# Goldfish_BigBoard_2-_revisions_after_pro.net
KiCad netlist of a schematic drawn in EAGLE
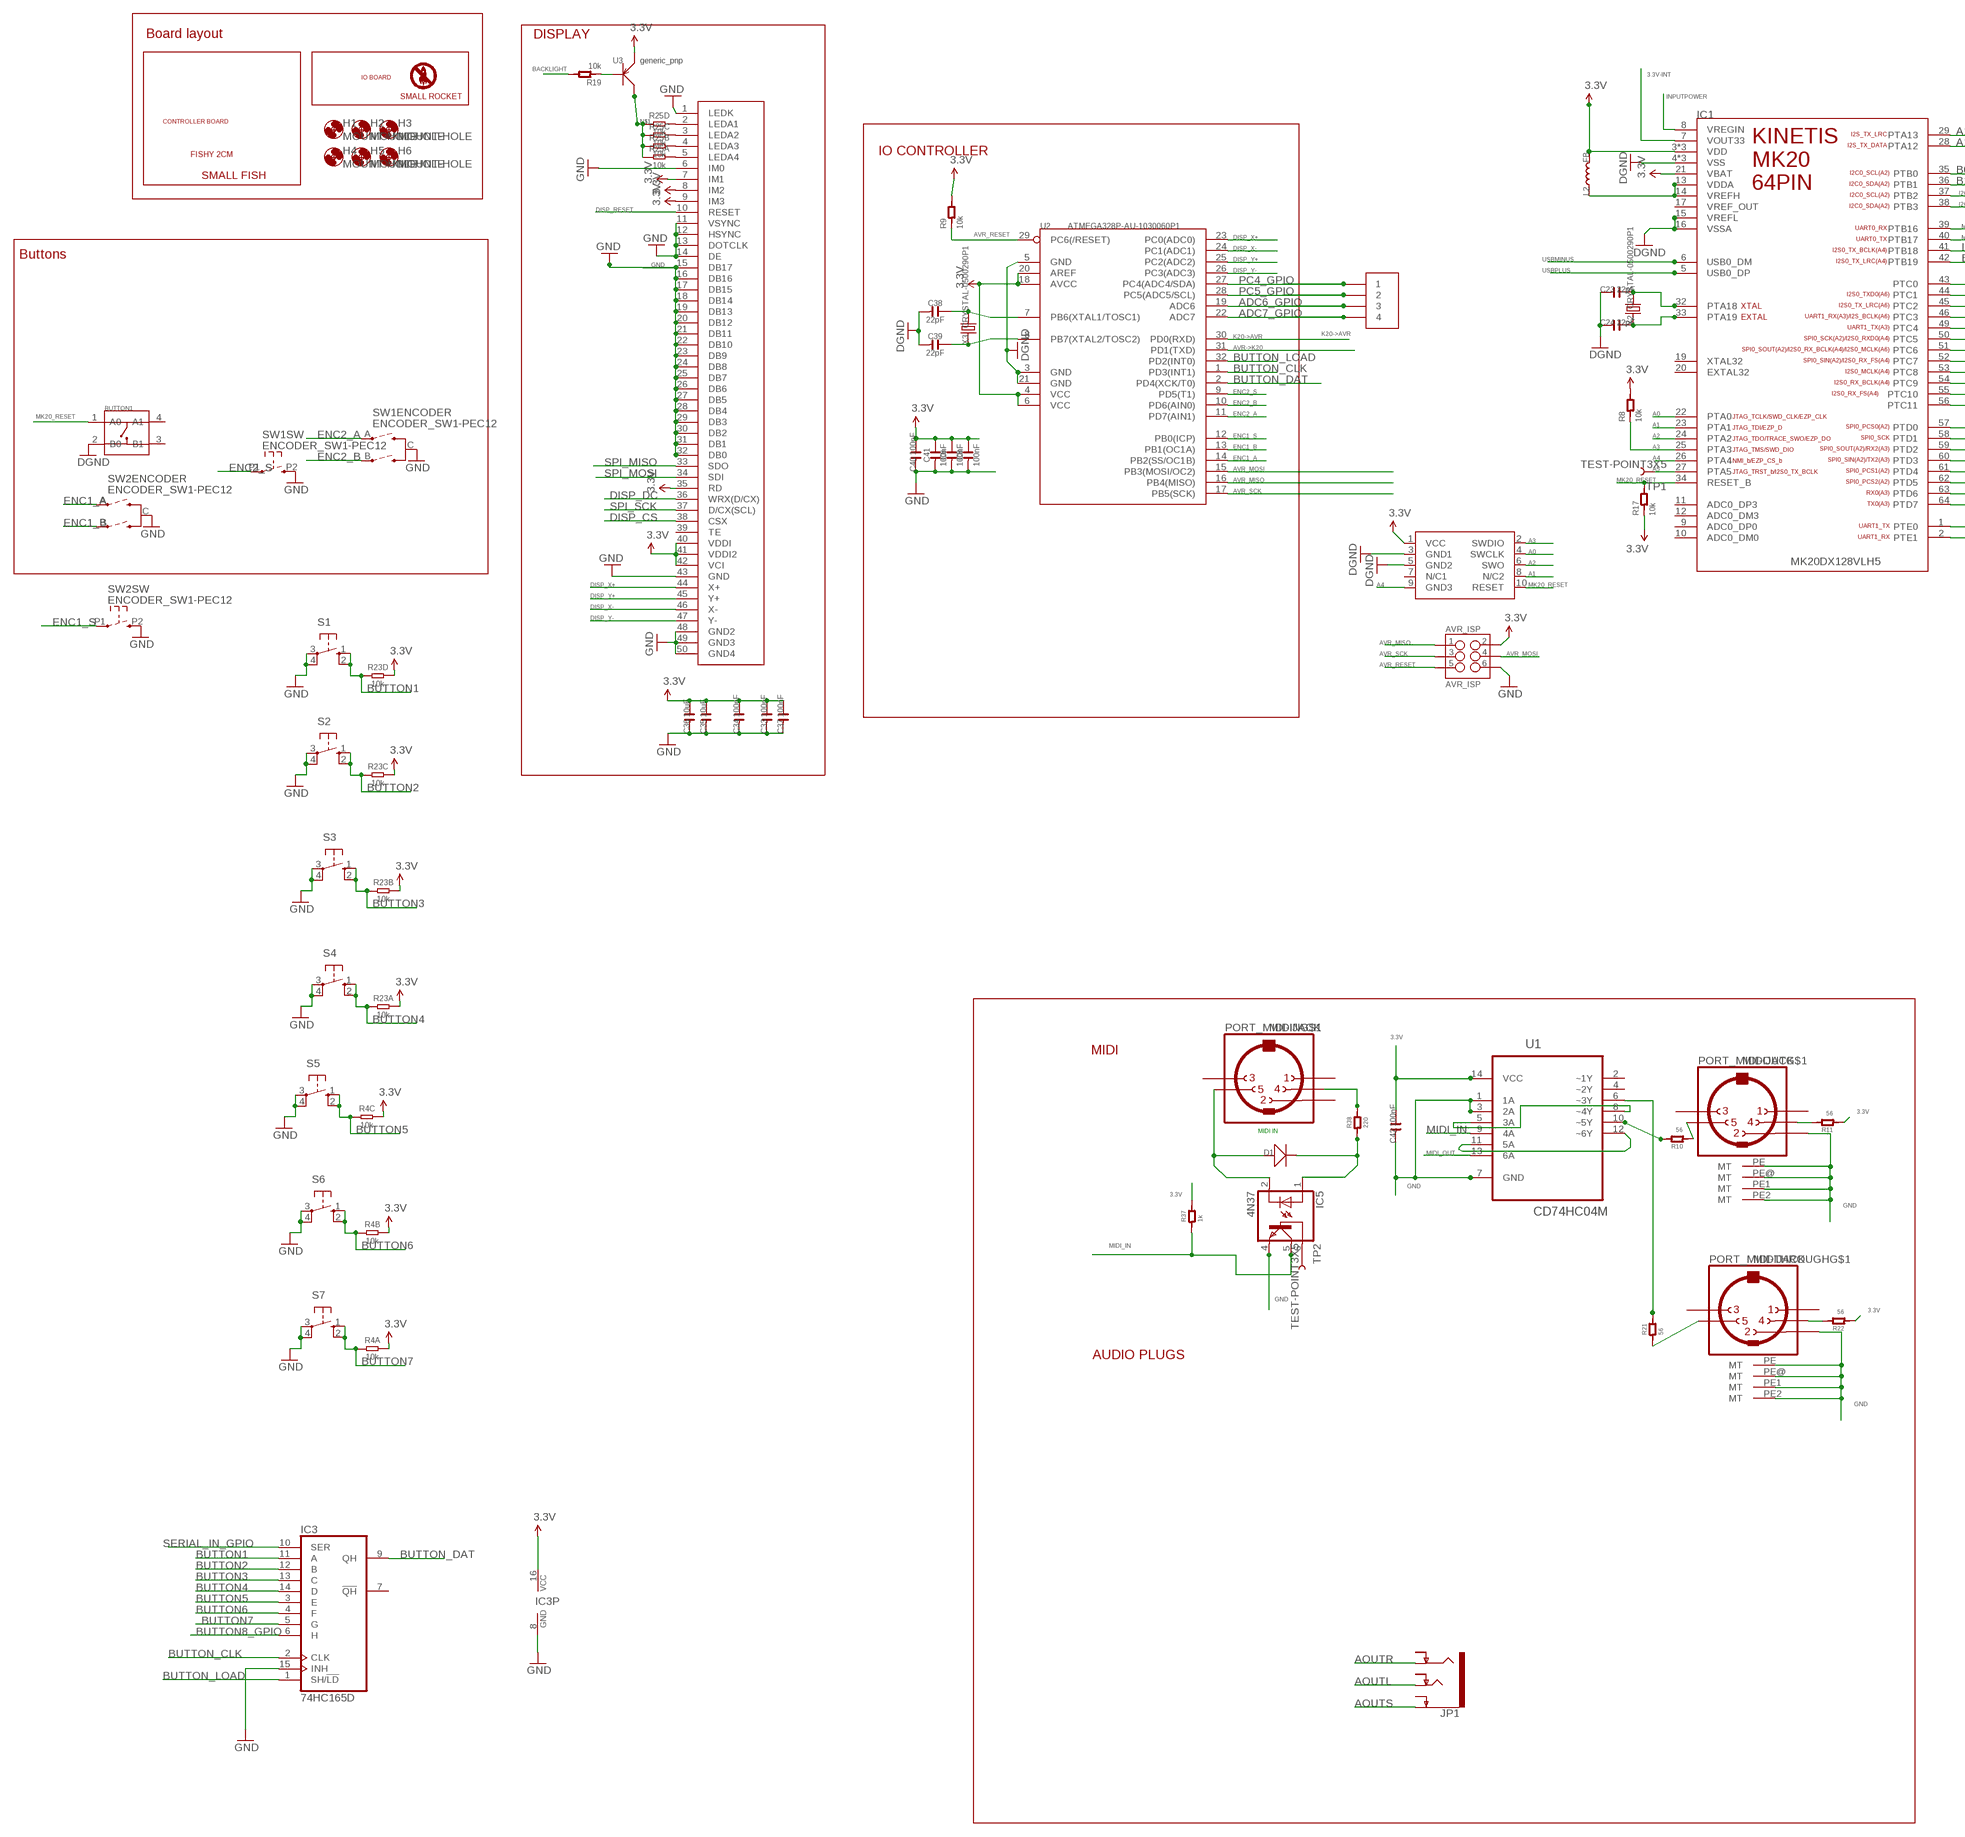
[diagram p0: schematic, sheet 1, part 1 of 3]
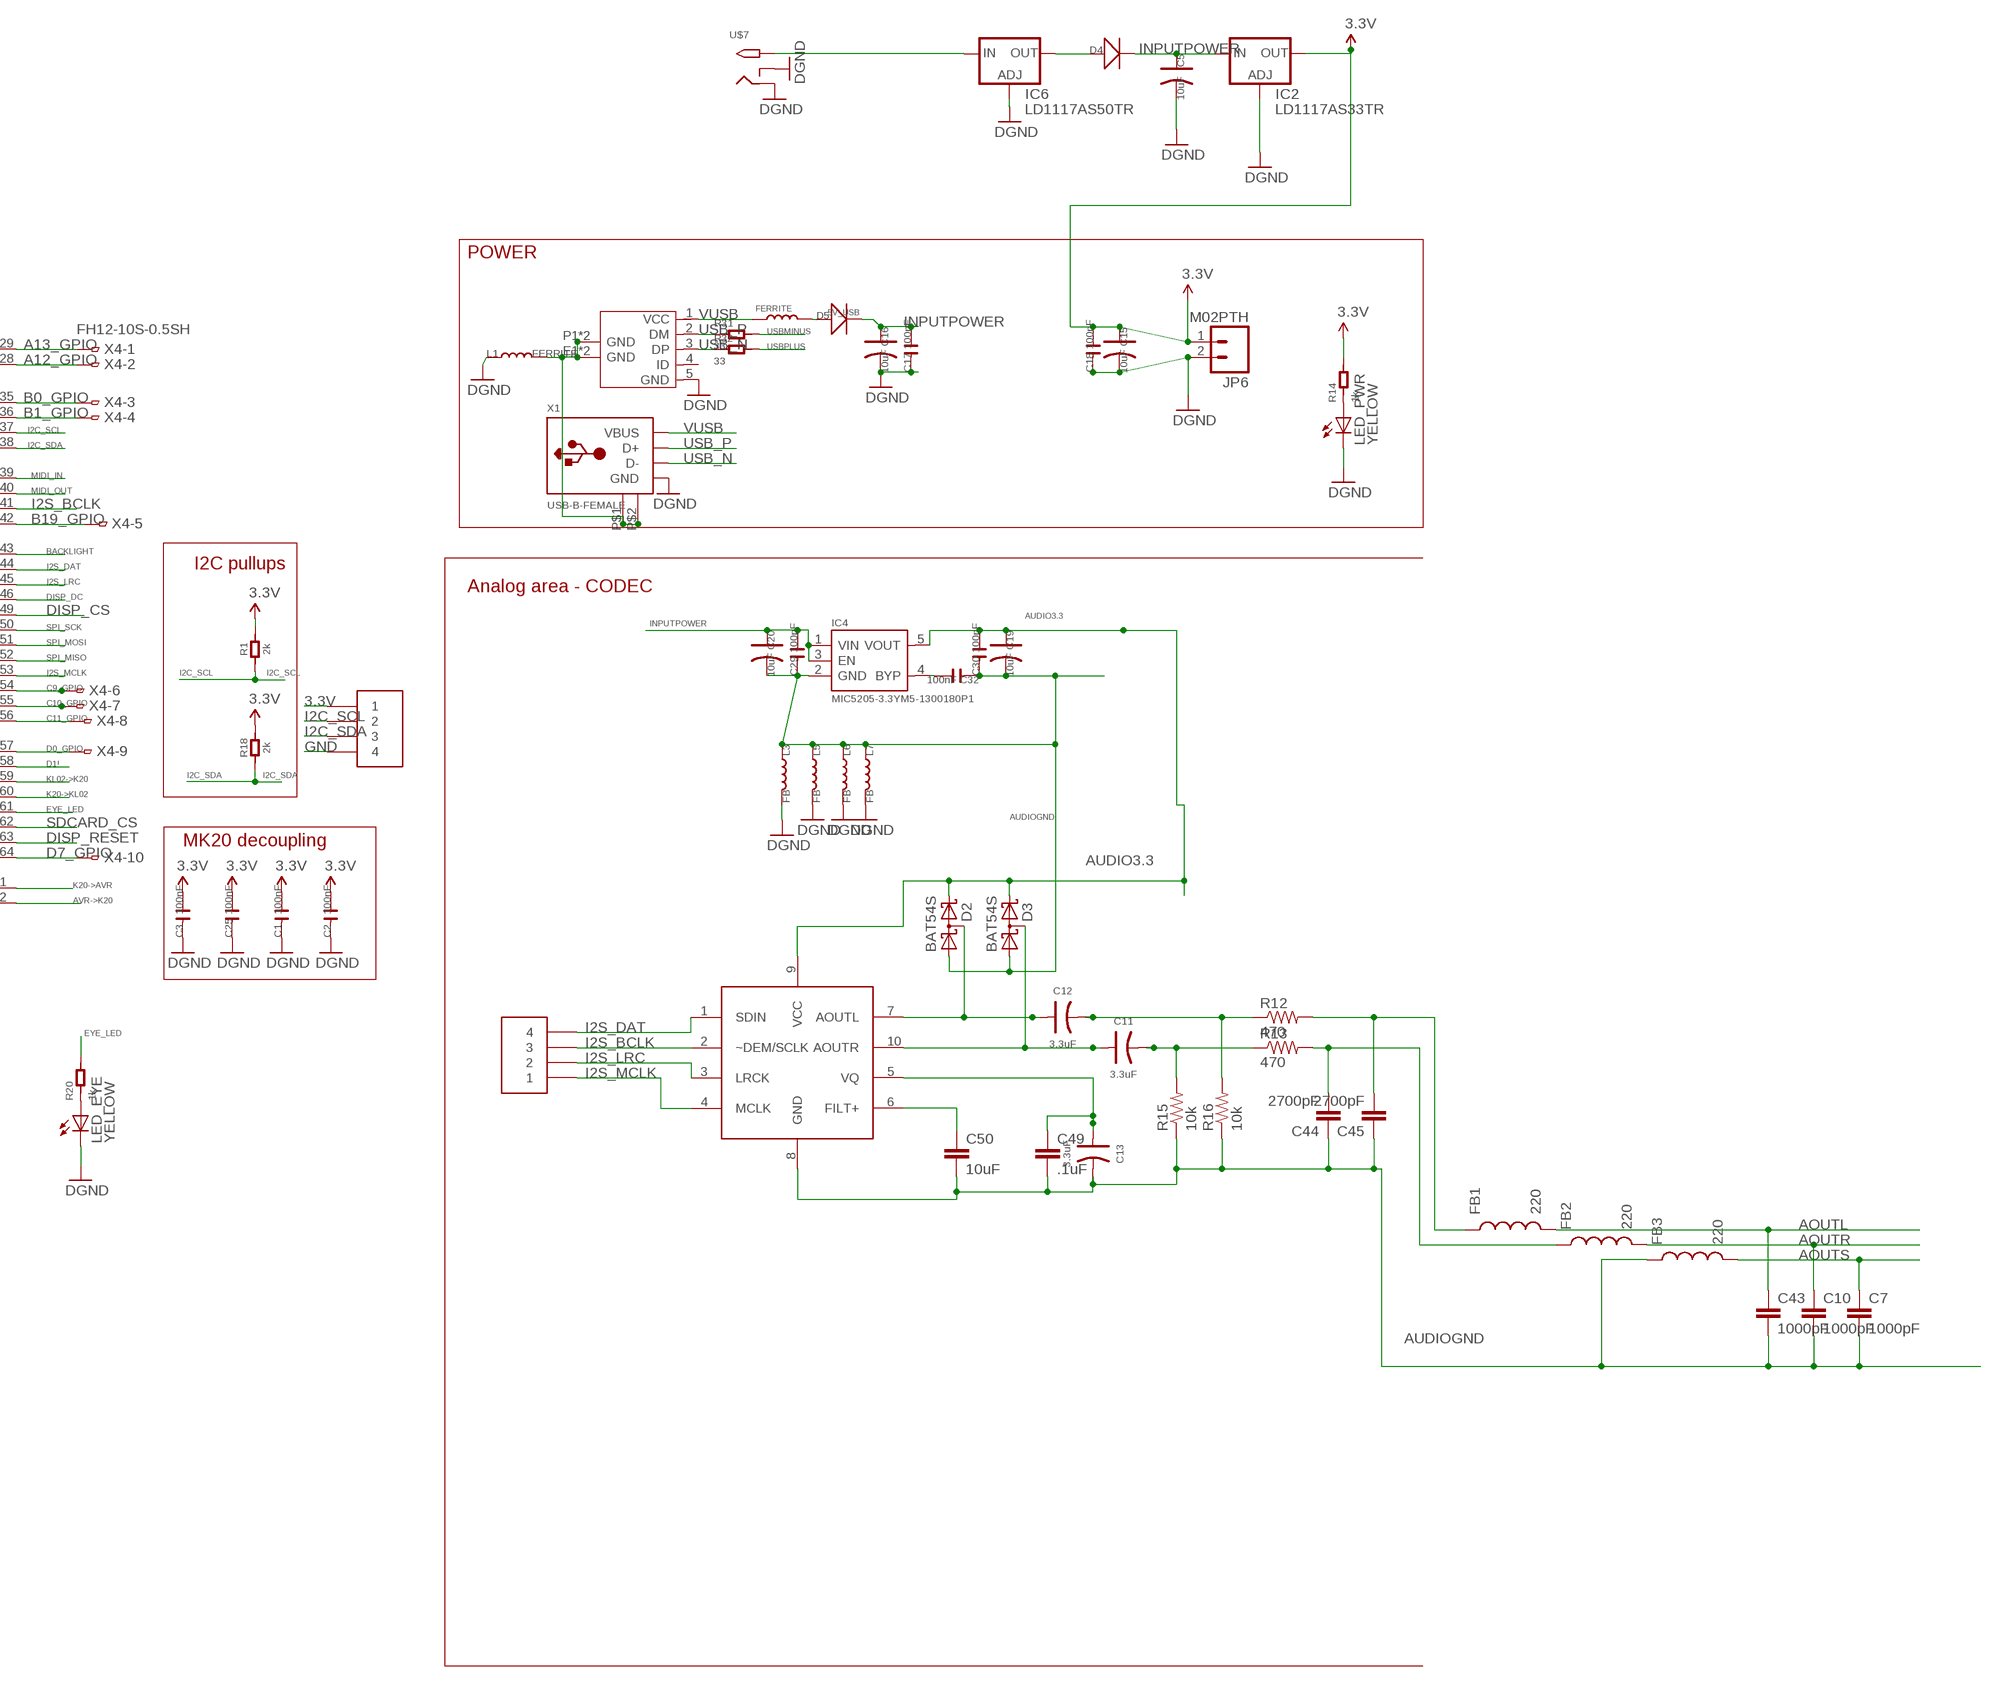
[diagram p1: schematic, sheet 1, part 2 of 3]
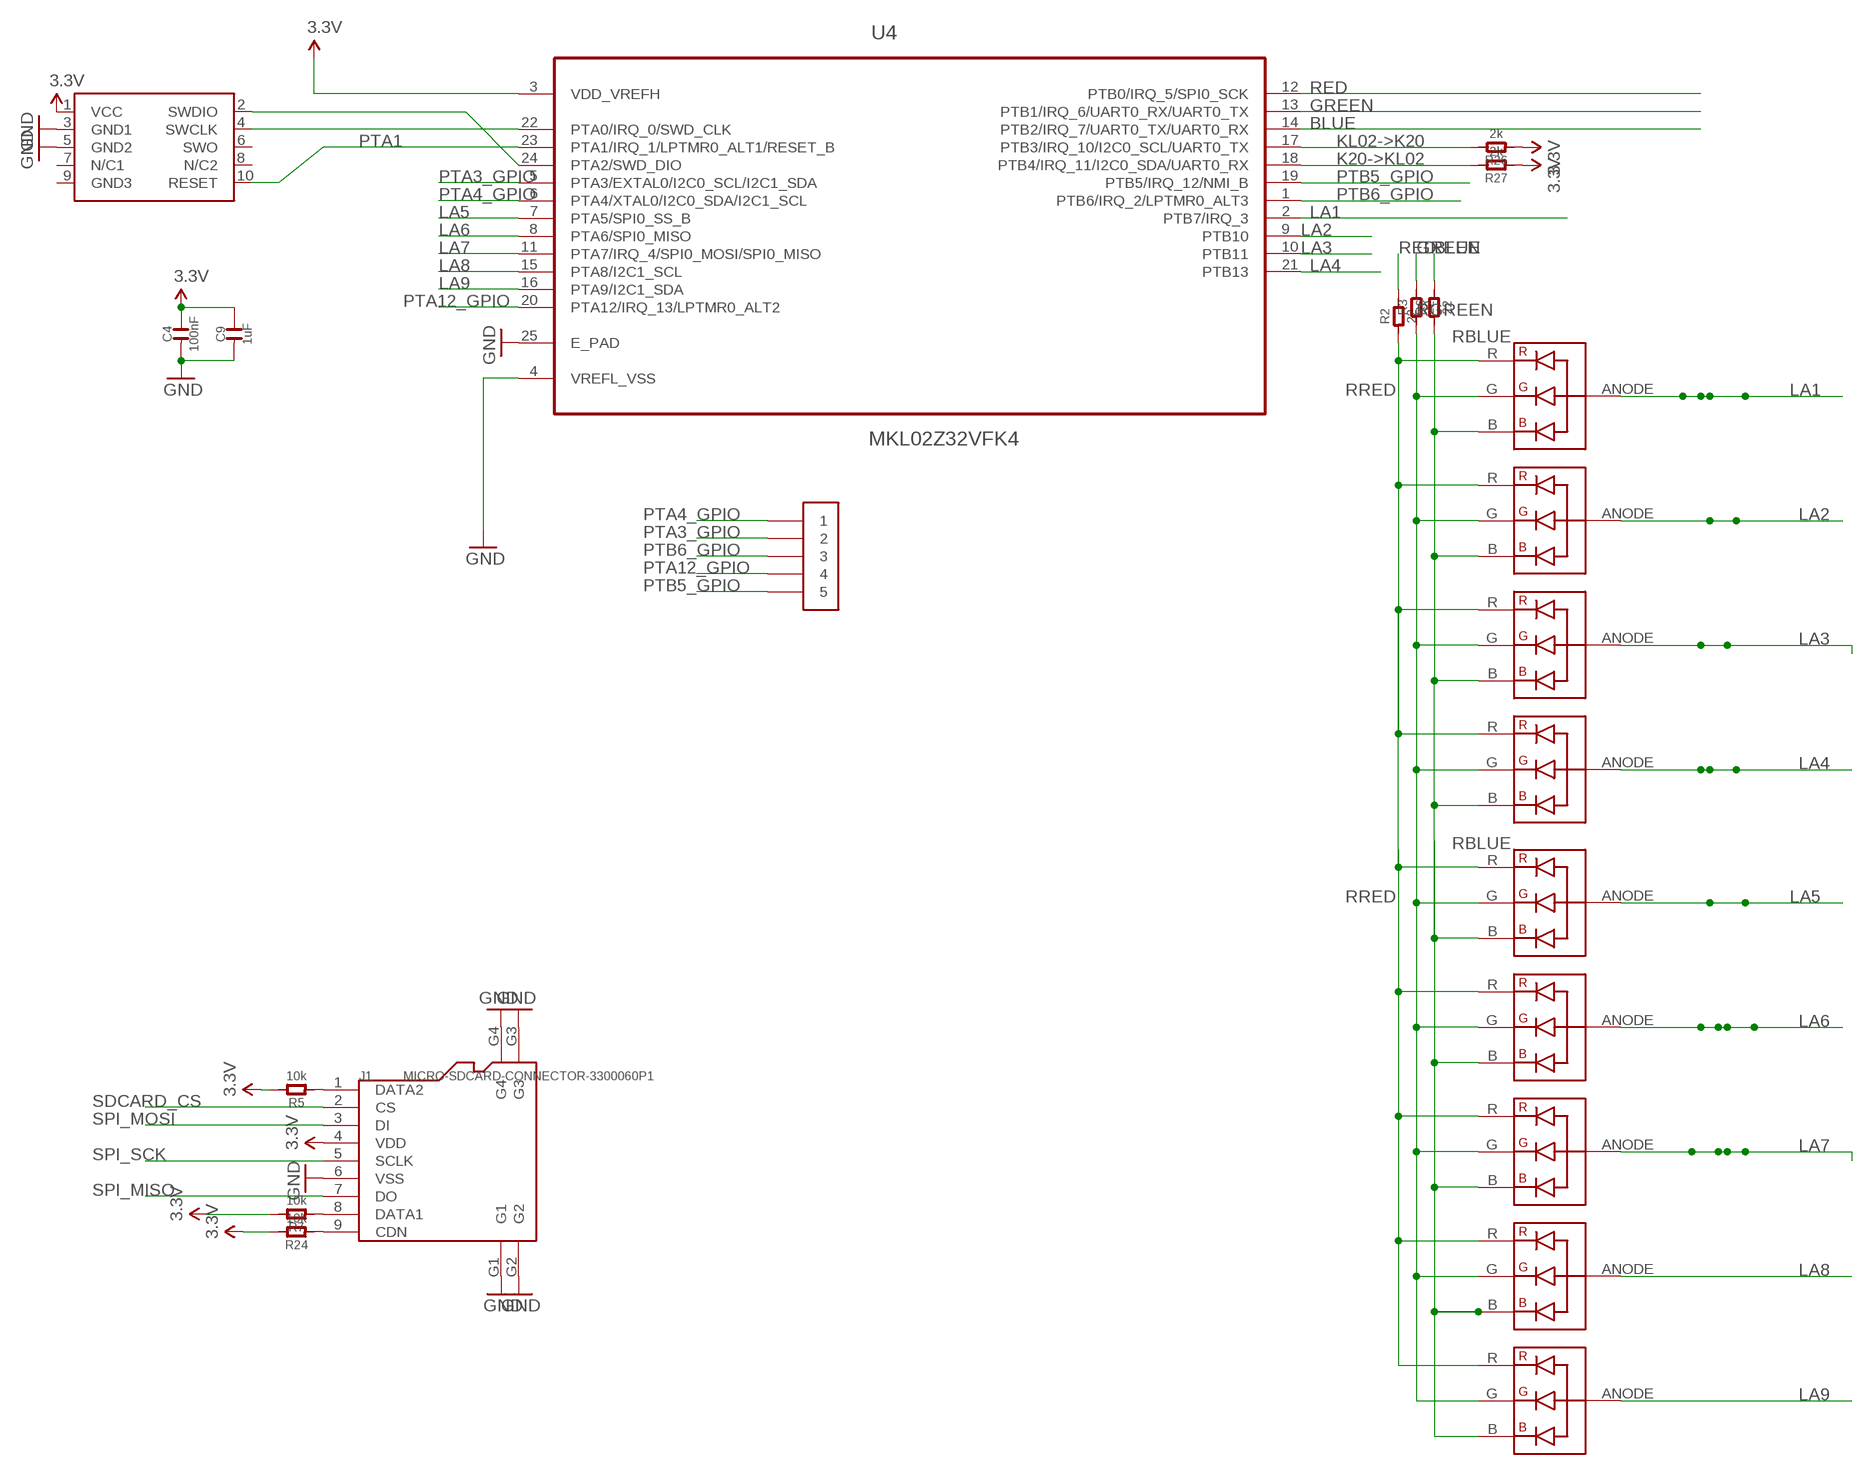
[diagram p2: schematic, sheet 1, part 3 of 3]

(export (version "E")
  (design (tool "Eeschema 10.0.6"))
  (components
    (comp (ref "AVR_ISP")
      (value "AVR_ISP")
      (footprint "eagle-import:2X3_SMT_POSTS")
      (libsource (lib "eagle-import") (part "M03X2SMT"))
    )
    (comp (ref "BUTTON1")
      (value "BUTTON-4P-3100010P1")
      (footprint "eagle-import:4P-SMD-6.0X6.0X5.0H")
      (libsource (lib "eagle-import") (part "BUTTON-4P-3100010P1"))
    )
    (comp (ref "C1")
      (value "100nF")
      (footprint "eagle-import:C0603")
      (libsource (lib "eagle-import") (part "OPL Eagle Library_C-0603"))
    )
    (comp (ref "C2")
      (value "100nF")
      (footprint "eagle-import:C0603")
      (libsource (lib "eagle-import") (part "OPL Eagle Library_C-0603"))
    )
    (comp (ref "C3")
      (value "100nF")
      (footprint "eagle-import:C0603")
      (libsource (lib "eagle-import") (part "OPL Eagle Library_C-0603"))
    )
    (comp (ref "C4")
      (value "100nF")
      (footprint "eagle-import:C0603")
      (libsource (lib "eagle-import") (part "C-0603"))
    )
    (comp (ref "C5")
      (value "10uF")
      (footprint "eagle-import:AVX-A")
      (libsource (lib "eagle-import") (part "OPL Eagle Library_C-POLAR-A"))
    )
    (comp (ref "C6")
      (value "100nF")
      (footprint "eagle-import:C0603")
      (libsource (lib "eagle-import") (part "C-0603"))
    )
    (comp (ref "C7")
      (value "1000pF")
      (footprint "eagle-import:0402-CAP")
      (libsource (lib "eagle-import") (part "CAP0402-CAP"))
    )
    (comp (ref "C8")
      (value "100nF")
      (footprint "eagle-import:C0603")
      (libsource (lib "eagle-import") (part "C-0603"))
    )
    (comp (ref "C9")
      (value "1uF")
      (footprint "eagle-import:C0603")
      (libsource (lib "eagle-import") (part "C-0603"))
    )
    (comp (ref "C10")
      (value "1000pF")
      (footprint "eagle-import:0402-CAP")
      (libsource (lib "eagle-import") (part "CAP0402-CAP"))
    )
    (comp (ref "C11")
      (value "3.3uF")
      (footprint "eagle-import:AVX-A")
      (libsource (lib "eagle-import") (part "C-POLAR-A"))
    )
    (comp (ref "C12")
      (value "3.3uF")
      (footprint "eagle-import:AVX-A")
      (libsource (lib "eagle-import") (part "C-POLAR-A"))
    )
    (comp (ref "C13")
      (value "3.3uF")
      (footprint "eagle-import:AVX-A")
      (libsource (lib "eagle-import") (part "C-POLAR-A"))
    )
    (comp (ref "C15")
      (value "10uF")
      (footprint "eagle-import:AVX-A")
      (libsource (lib "eagle-import") (part "OPL Eagle Library_C-POLAR-A"))
    )
    (comp (ref "C16")
      (value "10uF")
      (footprint "eagle-import:AVX-A")
      (libsource (lib "eagle-import") (part "OPL Eagle Library_C-POLAR-A"))
    )
    (comp (ref "C17")
      (value "100nF")
      (footprint "eagle-import:C0603")
      (libsource (lib "eagle-import") (part "OPL Eagle Library_C-0603"))
    )
    (comp (ref "C18")
      (value "100nF")
      (footprint "eagle-import:C0603")
      (libsource (lib "eagle-import") (part "OPL Eagle Library_C-0603"))
    )
    (comp (ref "C19")
      (value "10uF")
      (footprint "eagle-import:AVX-A")
      (libsource (lib "eagle-import") (part "OPL Eagle Library_C-POLAR-A"))
    )
    (comp (ref "C20")
      (value "10uF")
      (footprint "eagle-import:AVX-A")
      (libsource (lib "eagle-import") (part "OPL Eagle Library_C-POLAR-A"))
    )
    (comp (ref "C23")
      (value "22pF")
      (footprint "eagle-import:C0603")
      (libsource (lib "eagle-import") (part "OPL Eagle Library_C-0603"))
    )
    (comp (ref "C24")
      (value "22pF")
      (footprint "eagle-import:C0603")
      (libsource (lib "eagle-import") (part "OPL Eagle Library_C-0603"))
    )
    (comp (ref "C25")
      (value "100nF")
      (footprint "eagle-import:C0603")
      (libsource (lib "eagle-import") (part "OPL Eagle Library_C-0603"))
    )
    (comp (ref "C29")
      (value "100nF")
      (footprint "eagle-import:C0603")
      (libsource (lib "eagle-import") (part "OPL Eagle Library_C-0603"))
    )
    (comp (ref "C30")
      (value "100nF")
      (footprint "eagle-import:C0603")
      (libsource (lib "eagle-import") (part "OPL Eagle Library_C-0603"))
    )
    (comp (ref "C32")
      (value "100nF")
      (footprint "eagle-import:C0603")
      (libsource (lib "eagle-import") (part "OPL Eagle Library_C-0603"))
    )
    (comp (ref "C33")
      (value "100nF")
      (footprint "eagle-import:C0603")
      (libsource (lib "eagle-import") (part "OPL Eagle Library_C-0603"))
    )
    (comp (ref "C34")
      (value "100nF")
      (footprint "eagle-import:C0603")
      (libsource (lib "eagle-import") (part "OPL Eagle Library_C-0603"))
    )
    (comp (ref "C35")
      (value "10uF")
      (footprint "eagle-import:C0603")
      (libsource (lib "eagle-import") (part "OPL Eagle Library_C-0603"))
    )
    (comp (ref "C36")
      (value "10uF")
      (footprint "eagle-import:C0805")
      (libsource (lib "eagle-import") (part "OPL Eagle Library_C-0805"))
    )
    (comp (ref "C37")
      (value "100nF")
      (footprint "eagle-import:C0805")
      (libsource (lib "eagle-import") (part "OPL Eagle Library_C-0805"))
    )
    (comp (ref "C38")
      (value "22pF")
      (footprint "eagle-import:C0603")
      (libsource (lib "eagle-import") (part "C-0603"))
    )
    (comp (ref "C39")
      (value "22pF")
      (footprint "eagle-import:C0603")
      (libsource (lib "eagle-import") (part "C-0603"))
    )
    (comp (ref "C40")
      (value "100nF")
      (footprint "eagle-import:C0603")
      (libsource (lib "eagle-import") (part "OPL Eagle Library_C-0603"))
    )
    (comp (ref "C41")
      (value "100nF")
      (footprint "eagle-import:C0603")
      (libsource (lib "eagle-import") (part "C-0603"))
    )
    (comp (ref "C42")
      (value "100nF")
      (footprint "eagle-import:C0603")
      (libsource (lib "eagle-import") (part "OPL Eagle Library_C-0603"))
    )
    (comp (ref "C43")
      (value "1000pF")
      (footprint "eagle-import:0402-CAP")
      (libsource (lib "eagle-import") (part "CAP0402-CAP"))
    )
    (comp (ref "C44")
      (value "2700pF")
      (footprint "eagle-import:0402-CAP")
      (libsource (lib "eagle-import") (part "CAP0402-CAP"))
    )
    (comp (ref "C45")
      (value "2700pF")
      (footprint "eagle-import:0402-CAP")
      (libsource (lib "eagle-import") (part "CAP0402-CAP"))
    )
    (comp (ref "C49")
      (value ".1uF")
      (footprint "eagle-import:0402-CAP")
      (libsource (lib "eagle-import") (part "CAP0402-CAP"))
    )
    (comp (ref "C50")
      (value "10uF")
      (footprint "eagle-import:0402-CAP")
      (libsource (lib "eagle-import") (part "CAP0402-CAP"))
    )
    (comp (ref "D1")
      (value "D-D1206")
      (footprint "eagle-import:LL-34")
      (libsource (lib "eagle-import") (part "D-D1206"))
    )
    (comp (ref "D2")
      (value "BAT54S")
      (footprint "eagle-import:SOT23")
      (libsource (lib "eagle-import") (part "BAT54S"))
    )
    (comp (ref "D3")
      (value "BAT54S")
      (footprint "eagle-import:SOT23")
      (libsource (lib "eagle-import") (part "BAT54S"))
    )
    (comp (ref "D4")
      (value "D-D1206")
      (footprint "eagle-import:LL-34")
      (libsource (lib "eagle-import") (part "D-D1206"))
    )
    (comp (ref "D5")
      (value "D-D1206")
      (footprint "eagle-import:LL-34")
      (libsource (lib "eagle-import") (part "D-D1206"))
    )
    (comp (ref "FB1")
      (value "220")
      (footprint "eagle-import:0805")
      (libsource (lib "eagle-import") (part "INDUCTOR0805"))
    )
    (comp (ref "FB2")
      (value "220")
      (footprint "eagle-import:0805")
      (libsource (lib "eagle-import") (part "INDUCTOR0805"))
    )
    (comp (ref "FB3")
      (value "220")
      (footprint "eagle-import:0805")
      (libsource (lib "eagle-import") (part "INDUCTOR0805"))
    )
    (comp (ref "H1")
      (value "MOUNT-HOLE")
      (footprint "eagle-import:3.2-NOMARKINGS-SMALLSAFEZONE")
      (libsource (lib "eagle-import") (part "MOUNT-HOLE"))
    )
    (comp (ref "H2")
      (value "MOUNT-HOLE")
      (footprint "eagle-import:3.2-NOMARKINGS-SMALLSAFEZONE")
      (libsource (lib "eagle-import") (part "MOUNT-HOLE"))
    )
    (comp (ref "H3")
      (value "MOUNT-HOLE")
      (footprint "eagle-import:3.2-NOMARKINGS-SMALLSAFEZONE")
      (libsource (lib "eagle-import") (part "MOUNT-HOLE"))
    )
    (comp (ref "H4")
      (value "MOUNT-HOLE")
      (footprint "eagle-import:3.2-NOMARKINGS-SMALLSAFEZONE")
      (libsource (lib "eagle-import") (part "MOUNT-HOLE"))
    )
    (comp (ref "H5")
      (value "MOUNT-HOLE")
      (footprint "eagle-import:3.2-NOMARKINGS-SMALLSAFEZONE")
      (libsource (lib "eagle-import") (part "MOUNT-HOLE"))
    )
    (comp (ref "H6")
      (value "MOUNT-HOLE")
      (footprint "eagle-import:3.2-NOMARKINGS-SMALLSAFEZONE")
      (libsource (lib "eagle-import") (part "MOUNT-HOLE"))
    )
    (comp (ref "IC1")
      (value "MK20DX128VLH5")
      (footprint "eagle-import:MK20DX128VLH5")
      (libsource (lib "eagle-import") (part "MK20DX128VLH5"))
    )
    (comp (ref "IC2")
      (value "LD1117AS33TR")
      (footprint "eagle-import:SOT223")
      (libsource (lib "eagle-import") (part "LD1117A?S33TR"))
    )
    (comp (ref "IC3")
      (value "74HC165D")
      (footprint "eagle-import:SO16")
      (libsource (lib "eagle-import") (part "74165DHC"))
    )
    (comp (ref "IC4")
      (value "MIC5205-3.3YM5-1300180P1")
      (footprint "eagle-import:SOT23-5")
      (libsource (lib "eagle-import") (part "MIC5205-3.3YM5-1300180P1"))
    )
    (comp (ref "IC5")
      (value "4N37")
      (footprint "eagle-import:DIL06")
      (fields (field (name "MF") "FAIRCHILD SEMICONDUCTOR"))
      (libsource (lib "eagle-import") (part "4N37"))
    )
    (comp (ref "IC6")
      (value "LD1117AS50TR")
      (footprint "eagle-import:SOT223")
      (libsource (lib "eagle-import") (part "LD1117A?S50TR"))
    )
    (comp (ref "J1")
      (value "MICRO-SDCARD-CONNECTOR-3300060P1")
      (footprint "eagle-import:9P-SMD-W-RING")
      (libsource (lib "eagle-import") (part "MICRO-SDCARD-CONNECTOR-3300060P1"))
    )
    (comp (ref "J2")
      (value "MICRO-USB-5P-340015001")
      (footprint "eagle-import:B-SMD-5P")
      (libsource (lib "eagle-import") (part "MICRO-USB-5P-340015001"))
    )
    (comp (ref "JP1")
      (value "AUDIO-JACK4-.25-HORIZ-TRS")
      (footprint "eagle-import:AUDIO-JACK-.25-INCH-HORIZ-PTH")
      (libsource (lib "eagle-import") (part "AUDIO-JACK4-.25-HORIZ-TRS"))
    )
    (comp (ref "JP6")
      (value "M02PTH")
      (footprint "eagle-import:1X02")
      (libsource (lib "eagle-import") (part "M02PTH"))
    )
    (comp (ref "L1")
      (value "FERRITE")
      (footprint "eagle-import:L0603")
      (libsource (lib "eagle-import") (part "L-0603"))
    )
    (comp (ref "L2")
      (value "FB")
      (footprint "eagle-import:L0603")
      (libsource (lib "eagle-import") (part "L-0603"))
    )
    (comp (ref "L3")
      (value "FB")
      (footprint "eagle-import:L0603")
      (libsource (lib "eagle-import") (part "L-0603"))
    )
    (comp (ref "L4")
      (value "FERRITE")
      (footprint "eagle-import:L0603")
      (libsource (lib "eagle-import") (part "L-0603"))
    )
    (comp (ref "L5")
      (value "FB")
      (footprint "eagle-import:L0603")
      (libsource (lib "eagle-import") (part "L-0603"))
    )
    (comp (ref "L6")
      (value "FB")
      (footprint "eagle-import:L0603")
      (libsource (lib "eagle-import") (part "L-0603"))
    )
    (comp (ref "L7")
      (value "FB")
      (footprint "eagle-import:L0603")
      (libsource (lib "eagle-import") (part "L-0603"))
    )
    (comp (ref "LED_EYE")
      (value "YELLOW")
      (footprint "eagle-import:CHIP-LED0603")
      (libsource (lib "eagle-import") (part "LEDCHIP-LED0603"))
    )
    (comp (ref "LED_PWR")
      (value "YELLOW")
      (footprint "eagle-import:CHIP-LED0603")
      (libsource (lib "eagle-import") (part "LEDCHIP-LED0603"))
    )
    (comp (ref "PORT_MIDI-IN")
      (value "MIDIJACK")
      (footprint "eagle-import:CP-2350")
      (libsource (lib "eagle-import") (part "MIDIJACK"))
    )
    (comp (ref "PORT_MIDI-OUT")
      (value "MIDIJACK")
      (footprint "eagle-import:CP-2350")
      (libsource (lib "eagle-import") (part "MIDIJACK"))
    )
    (comp (ref "PORT_MIDI-THROUGH")
      (value "MIDIJACK")
      (footprint "eagle-import:CP-2350")
      (libsource (lib "eagle-import") (part "MIDIJACK"))
    )
    (comp (ref "R1")
      (value "2k")
      (footprint "eagle-import:R0603")
      (libsource (lib "eagle-import") (part "R-0603"))
    )
    (comp (ref "R2")
      (value "22")
      (footprint "eagle-import:R0603")
      (libsource (lib "eagle-import") (part "R-0603"))
    )
    (comp (ref "R3")
      (value "22")
      (footprint "eagle-import:R0603")
      (libsource (lib "eagle-import") (part "R-0603"))
    )
    (comp (ref "R4")
      (value "10k")
      (footprint "eagle-import:R1206-8")
      (libsource (lib "eagle-import") (part "R-4R"))
    )
    (comp (ref "R5")
      (value "10k")
      (footprint "eagle-import:R0603")
      (libsource (lib "eagle-import") (part "R-0603"))
    )
    (comp (ref "R6")
      (value "22")
      (footprint "eagle-import:R0603")
      (libsource (lib "eagle-import") (part "R-0603"))
    )
    (comp (ref "R7")
      (value "10k")
      (footprint "eagle-import:R0603")
      (libsource (lib "eagle-import") (part "R-0603"))
    )
    (comp (ref "R8")
      (value "10k")
      (footprint "eagle-import:R0603")
      (libsource (lib "eagle-import") (part "OPL Eagle Library_R-0603"))
    )
    (comp (ref "R9")
      (value "10k")
      (footprint "eagle-import:R0603")
      (libsource (lib "eagle-import") (part "OPL Eagle Library_R-0603"))
    )
    (comp (ref "R10")
      (value "56")
      (footprint "eagle-import:R0603")
      (libsource (lib "eagle-import") (part "OPL Eagle Library_R-0603"))
    )
    (comp (ref "R11")
      (value "56")
      (footprint "eagle-import:R0603")
      (libsource (lib "eagle-import") (part "OPL Eagle Library_R-0603"))
    )
    (comp (ref "R12")
      (value "470")
      (footprint "eagle-import:0603-RES")
      (libsource (lib "eagle-import") (part "RESISTOR0603-RES"))
    )
    (comp (ref "R13")
      (value "470")
      (footprint "eagle-import:0603-RES")
      (libsource (lib "eagle-import") (part "RESISTOR0603-RES"))
    )
    (comp (ref "R14")
      (value "1k")
      (footprint "eagle-import:R0603")
      (libsource (lib "eagle-import") (part "OPL Eagle Library_R-0603"))
    )
    (comp (ref "R15")
      (value "10k")
      (footprint "eagle-import:0603-RES")
      (libsource (lib "eagle-import") (part "RESISTOR0603-RES"))
    )
    (comp (ref "R16")
      (value "10k")
      (footprint "eagle-import:0603-RES")
      (libsource (lib "eagle-import") (part "RESISTOR0603-RES"))
    )
    (comp (ref "R17")
      (value "10k")
      (footprint "eagle-import:R0603")
      (libsource (lib "eagle-import") (part "OPL Eagle Library_R-0603"))
    )
    (comp (ref "R18")
      (value "2k")
      (footprint "eagle-import:R0603")
      (libsource (lib "eagle-import") (part "R-0603"))
    )
    (comp (ref "R19")
      (value "10k")
      (footprint "eagle-import:R0603")
      (libsource (lib "eagle-import") (part "OPL Eagle Library_R-0603"))
    )
    (comp (ref "R20")
      (value "1k")
      (footprint "eagle-import:R0603")
      (libsource (lib "eagle-import") (part "OPL Eagle Library_R-0603"))
    )
    (comp (ref "R21")
      (value "56")
      (footprint "eagle-import:R0603")
      (libsource (lib "eagle-import") (part "OPL Eagle Library_R-0603"))
    )
    (comp (ref "R22")
      (value "56")
      (footprint "eagle-import:R0603")
      (libsource (lib "eagle-import") (part "OPL Eagle Library_R-0603"))
    )
    (comp (ref "R23")
      (value "10k")
      (footprint "eagle-import:R1206-8")
      (libsource (lib "eagle-import") (part "R-4R"))
    )
    (comp (ref "R24")
      (value "10k")
      (footprint "eagle-import:R0603")
      (libsource (lib "eagle-import") (part "R-0603"))
    )
    (comp (ref "R25")
      (value "10k")
      (footprint "eagle-import:R1206-8")
      (libsource (lib "eagle-import") (part "R-4R"))
    )
    (comp (ref "R26")
      (value "2k")
      (footprint "eagle-import:R0603")
      (libsource (lib "eagle-import") (part "R-0603"))
    )
    (comp (ref "R27")
      (value "2k")
      (footprint "eagle-import:R0603")
      (libsource (lib "eagle-import") (part "R-0603"))
    )
    (comp (ref "R31")
      (value "33")
      (footprint "eagle-import:R0603")
      (libsource (lib "eagle-import") (part "OPL Eagle Library_R-0603"))
    )
    (comp (ref "R32")
      (value "33")
      (footprint "eagle-import:R0603")
      (libsource (lib "eagle-import") (part "OPL Eagle Library_R-0603"))
    )
    (comp (ref "R37")
      (value "1k")
      (footprint "eagle-import:R0603")
      (libsource (lib "eagle-import") (part "OPL Eagle Library_R-0603"))
    )
    (comp (ref "R38")
      (value "220")
      (footprint "eagle-import:R0603")
      (libsource (lib "eagle-import") (part "OPL Eagle Library_R-0603"))
    )
    (comp (ref "S1")
      (value "40-XX-ROUND")
      (footprint "eagle-import:B3F-40XX-ROUND")
      (libsource (lib "eagle-import") (part "40-XX-ROUND"))
    )
    (comp (ref "S2")
      (value "40-XX-ROUND")
      (footprint "eagle-import:B3F-40XX-ROUND")
      (libsource (lib "eagle-import") (part "40-XX-ROUND"))
    )
    (comp (ref "S3")
      (value "40-XX-ROUND")
      (footprint "eagle-import:B3F-40XX-ROUND")
      (libsource (lib "eagle-import") (part "40-XX-ROUND"))
    )
    (comp (ref "S4")
      (value "40-XX-ROUND")
      (footprint "eagle-import:B3F-40XX-ROUND")
      (libsource (lib "eagle-import") (part "40-XX-ROUND"))
    )
    (comp (ref "S5")
      (value "40-XX-ROUND")
      (footprint "eagle-import:B3F-40XX-ROUND")
      (libsource (lib "eagle-import") (part "40-XX-ROUND"))
    )
    (comp (ref "S6")
      (value "40-XX-ROUND")
      (footprint "eagle-import:B3F-40XX-ROUND")
      (libsource (lib "eagle-import") (part "40-XX-ROUND"))
    )
    (comp (ref "S7")
      (value "40-XX-ROUND")
      (footprint "eagle-import:B3F-40XX-ROUND")
      (libsource (lib "eagle-import") (part "40-XX-ROUND"))
    )
    (comp (ref "SW1")
      (value "ENCODER_SW1-PEC12")
      (footprint "eagle-import:PEC12_INCREMENTAL_ENCODER")
      (libsource (lib "eagle-import") (part "ENCODER_SW1-PEC12"))
    )
    (comp (ref "SW2")
      (value "ENCODER_SW1-PEC12")
      (footprint "eagle-import:PEC12_INCREMENTAL_ENCODER")
      (libsource (lib "eagle-import") (part "ENCODER_SW1-PEC12"))
    )
    (comp (ref "SWD1")
      (value "CORTEX_SWD")
      (footprint "eagle-import:M50-3600542")
      (libsource (lib "eagle-import") (part "CORTEX_SWD"))
    )
    (comp (ref "SWD2")
      (value "CORTEX_SWD")
      (footprint "eagle-import:M50-3600542")
      (libsource (lib "eagle-import") (part "CORTEX_SWD"))
    )
    (comp (ref "TP1")
      (value "TEST-POINT3X5")
      (footprint "eagle-import:PAD.03X.05")
      (libsource (lib "eagle-import") (part "TEST-POINT3X5"))
    )
    (comp (ref "TP2")
      (value "TEST-POINT3X5")
      (footprint "eagle-import:PAD.03X.05")
      (libsource (lib "eagle-import") (part "TEST-POINT3X5"))
    )
    (comp (ref "U$1")
      (value "2.8\"TFT2.8\"TFT")
      (footprint "eagle-import:2.8_TFT")
      (libsource (lib "eagle-import") (part "2.8{dblquote}TFT2.8{dblquote}TFT"))
    )
    (comp (ref "U$3")
      (value "FISH2CM_SILK")
      (footprint "eagle-import:FISH_WITHSILK")
      (libsource (lib "eagle-import") (part "FISH2CM_SILK"))
    )
    (comp (ref "U$4")
      (value "FISH_SMALL")
      (footprint "eagle-import:FISH_SMALL")
      (libsource (lib "eagle-import") (part "FISH_SMALL"))
    )
    (comp (ref "U$6")
      (value "CS4344-DAC")
      (footprint "eagle-import:TSSOP-10")
      (libsource (lib "eagle-import") (part "CS4344-DAC"))
    )
    (comp (ref "U$7")
      (value "2.1MMJACKTHM")
      (footprint "eagle-import:163-179PH-EX")
      (libsource (lib "eagle-import") (part "2.1MMJACKTHM"))
    )
    (comp (ref "U$8")
      (value "SMALLROCKET")
      (footprint "eagle-import:SMALLROCKET")
      (libsource (lib "eagle-import") (part "SMALLROCKET"))
    )
    (comp (ref "U$9")
      (value "RGBLED_COMMONANODE")
      (footprint "eagle-import:3.5X2.8_RGB_LED")
      (libsource (lib "eagle-import") (part "RGBLED_COMMONANODE"))
    )
    (comp (ref "U$10")
      (value "RGBLED_COMMONANODE")
      (footprint "eagle-import:3.5X2.8_RGB_LED")
      (libsource (lib "eagle-import") (part "RGBLED_COMMONANODE"))
    )
    (comp (ref "U$11")
      (value "M05")
      (footprint "eagle-import:M05")
      (libsource (lib "eagle-import") (part "M05"))
    )
    (comp (ref "U$12")
      (value "RGBLED_COMMONANODE")
      (footprint "eagle-import:3.5X2.8_RGB_LED")
      (libsource (lib "eagle-import") (part "RGBLED_COMMONANODE"))
    )
    (comp (ref "U$13")
      (value "RGBLED_COMMONANODE")
      (footprint "eagle-import:3.5X2.8_RGB_LED")
      (libsource (lib "eagle-import") (part "RGBLED_COMMONANODE"))
    )
    (comp (ref "U$14")
      (value "RGBLED_COMMONANODE")
      (footprint "eagle-import:3.5X2.8_RGB_LED")
      (libsource (lib "eagle-import") (part "RGBLED_COMMONANODE"))
    )
    (comp (ref "U$15")
      (value "RGBLED_COMMONANODE")
      (footprint "eagle-import:3.5X2.8_RGB_LED")
      (libsource (lib "eagle-import") (part "RGBLED_COMMONANODE"))
    )
    (comp (ref "U$16")
      (value "RGBLED_COMMONANODE")
      (footprint "eagle-import:3.5X2.8_RGB_LED")
      (libsource (lib "eagle-import") (part "RGBLED_COMMONANODE"))
    )
    (comp (ref "U$17")
      (value "RGBLED_COMMONANODE")
      (footprint "eagle-import:3.5X2.8_RGB_LED")
      (libsource (lib "eagle-import") (part "RGBLED_COMMONANODE"))
    )
    (comp (ref "U$18")
      (value "RGBLED_COMMONANODE")
      (footprint "eagle-import:3.5X2.8_RGB_LED")
      (libsource (lib "eagle-import") (part "RGBLED_COMMONANODE"))
    )
    (comp (ref "U$20")
      (value "M04")
      (footprint "eagle-import:M04")
      (libsource (lib "eagle-import") (part "M04"))
    )
    (comp (ref "U$21")
      (value "M04")
      (footprint "eagle-import:M04")
      (libsource (lib "eagle-import") (part "M04"))
    )
    (comp (ref "U$22")
      (value "M04")
      (footprint "eagle-import:M04")
      (libsource (lib "eagle-import") (part "M04"))
    )
    (comp (ref "U1")
      (value "CD74HC04M")
      (footprint "eagle-import:SOIC127P600X175-14N")
      (libsource (lib "eagle-import") (part "CD74HC04M"))
    )
    (comp (ref "U2")
      (value "ATMEGA328P-AU-1030060P1")
      (footprint "eagle-import:TQFP32")
      (libsource (lib "eagle-import") (part "ATMEGA328P-AU-1030060P1"))
    )
    (comp (ref "U3")
      (value "generic_pnp")
      (footprint "eagle-import:SOT23")
      (libsource (lib "eagle-import") (part "TRANSISTOR-PNP-041003001"))
    )
    (comp (ref "U4")
      (value "MKL02Z32VFK4")
      (footprint "eagle-import:QFN50P400X400X100-25N")
      (libsource (lib "eagle-import") (part "MKL02Z32VFK4"))
    )
    (comp (ref "X1")
      (value "USB-B-FEMALE")
      (footprint "eagle-import:FCI61729")
      (libsource (lib "eagle-import") (part "USB-B-FEMALE"))
    )
    (comp (ref "X2")
      (value "CRYSTAL-0500290P1")
      (footprint "eagle-import:2P-SMD-5.0X3.2")
      (libsource (lib "eagle-import") (part "OPL Eagle Library_CRYSTAL-0500290P1"))
    )
    (comp (ref "X3")
      (value "CRYSTAL-0500290P1")
      (footprint "eagle-import:2P-SMD-5.0X3.2")
      (libsource (lib "eagle-import") (part "CRYSTAL-0500290P1"))
    )
    (comp (ref "X4")
      (value "FH12-10S-0.5SH")
      (footprint "eagle-import:FH12-10S-0.5SH")
      (fields (field (name "MPN") "FH12-10S-0.5SH(55)"))
      (libsource (lib "eagle-import") (part "FH12-10S-0.5SH"))
    )
  )
  (nets
    (net (code "1") (name "/3.3V-INT") (class "Default")
      (node (ref "IC1") (pin "7") (pinfunction "VOUT33_7") (pintype "bidirectional"))
    )
    (net (code "2") (name "/5V_USB") (class "Default")
      (node (ref "D5") (pin "A") (pinfunction "+_A") (pintype "passive"))
      (node (ref "L4") (pin "2") (pinfunction "2_2") (pintype "passive"))
    )
    (net (code "3") (name "/A0") (class "Default")
      (node (ref "IC1") (pin "22") (pinfunction "PTA0_22") (pintype "bidirectional"))
      (node (ref "SWD1") (pin "4") (pinfunction "SWCLK_4") (pintype "bidirectional"))
    )
    (net (code "4") (name "/A1") (class "Default")
      (node (ref "IC1") (pin "23") (pinfunction "PTA1_23") (pintype "bidirectional"))
      (node (ref "SWD1") (pin "8") (pinfunction "N/C2_8") (pintype "bidirectional"))
    )
    (net (code "5") (name "/A2") (class "Default")
      (node (ref "IC1") (pin "24") (pinfunction "PTA2_24") (pintype "bidirectional"))
      (node (ref "SWD1") (pin "6") (pinfunction "SWO_6") (pintype "bidirectional"))
    )
    (net (code "6") (name "/A3") (class "Default")
      (node (ref "IC1") (pin "25") (pinfunction "PTA3_25") (pintype "bidirectional"))
      (node (ref "R8") (pin "1") (pinfunction "1_1") (pintype "bidirectional"))
      (node (ref "SWD1") (pin "2") (pinfunction "SWDIO_2") (pintype "bidirectional"))
    )
    (net (code "7") (name "/A4") (class "Default")
      (node (ref "IC1") (pin "26") (pinfunction "PTA4_26") (pintype "bidirectional"))
      (node (ref "SWD1") (pin "9") (pinfunction "GND3_9") (pintype "bidirectional"))
    )
    (net (code "8") (name "/A5") (class "Default")
      (node (ref "IC1") (pin "27") (pinfunction "PTA5_27") (pintype "bidirectional"))
      (node (ref "TP1") (pin "P$1") (pinfunction "1_P$1") (pintype "bidirectional"))
    )
    (net (code "9") (name "/A12_GPIO") (class "Default")
      (node (ref "IC1") (pin "28") (pinfunction "PTA12_28") (pintype "bidirectional"))
      (node (ref "X4") (pin "2") (pinfunction "1_2") (pintype "passive"))
    )
    (net (code "10") (name "/A13_GPIO") (class "Default")
      (node (ref "IC1") (pin "29") (pinfunction "PTA13_29") (pintype "bidirectional"))
      (node (ref "X4") (pin "1") (pinfunction "1_1") (pintype "passive"))
    )
    (net (code "11") (name "/ADC6_GPIO") (class "Default")
      (node (ref "U$20") (pin "P$3") (pinfunction "3_P$3") (pintype "bidirectional"))
      (node (ref "U2") (pin "19") (pinfunction "ADC6_19") (pintype "bidirectional"))
    )
    (net (code "12") (name "/ADC7_GPIO") (class "Default")
      (node (ref "U$20") (pin "P$4") (pinfunction "4_P$4") (pintype "bidirectional"))
      (node (ref "U2") (pin "22") (pinfunction "ADC7_22") (pintype "bidirectional"))
    )
    (net (code "13") (name "/AOUTL") (class "Default")
      (node (ref "C43") (pin "1") (pinfunction "1_1") (pintype "passive"))
      (node (ref "FB1") (pin "2") (pinfunction "2_2") (pintype "passive"))
      (node (ref "JP1") (pin "P$6") (pinfunction "TIP_P$6") (pintype "bidirectional"))
    )
    (net (code "14") (name "/AOUTR") (class "Default")
      (node (ref "C10") (pin "1") (pinfunction "1_1") (pintype "passive"))
      (node (ref "FB2") (pin "2") (pinfunction "2_2") (pintype "passive"))
      (node (ref "JP1") (pin "P$4") (pinfunction "RING_P$4") (pintype "bidirectional"))
    )
    (net (code "15") (name "/AOUTS") (class "Default")
      (node (ref "C7") (pin "1") (pinfunction "1_1") (pintype "passive"))
      (node (ref "FB3") (pin "2") (pinfunction "2_2") (pintype "passive"))
      (node (ref "JP1") (pin "P$2") (pinfunction "EARTH_P$2") (pintype "bidirectional"))
    )
    (net (code "16") (name "/AUDIO3.3") (class "Default")
      (node (ref "C19") (pin "+") (pinfunction "1_+") (pintype "bidirectional"))
      (node (ref "C30") (pin "2") (pinfunction "2_2") (pintype "bidirectional"))
      (node (ref "D2") (pin "2") (pinfunction "C2_2") (pintype "passive"))
      (node (ref "D3") (pin "2") (pinfunction "C2_2") (pintype "passive"))
      (node (ref "IC4") (pin "5") (pinfunction "VOUT_5") (pintype "bidirectional"))
      (node (ref "U$6") (pin "9") (pinfunction "VCC_9") (pintype "bidirectional"))
    )
    (net (code "17") (name "/AUDIOGND") (class "Default")
      (node (ref "C10") (pin "2") (pinfunction "2_2") (pintype "passive"))
      (node (ref "C13") (pin "-") (pinfunction "2_-") (pintype "bidirectional"))
      (node (ref "C19") (pin "-") (pinfunction "2_-") (pintype "bidirectional"))
      (node (ref "C20") (pin "-") (pinfunction "2_-") (pintype "bidirectional"))
      (node (ref "C29") (pin "1") (pinfunction "1_1") (pintype "bidirectional"))
      (node (ref "C30") (pin "1") (pinfunction "1_1") (pintype "bidirectional"))
      (node (ref "C32") (pin "1") (pinfunction "1_1") (pintype "bidirectional"))
      (node (ref "C43") (pin "2") (pinfunction "2_2") (pintype "passive"))
      (node (ref "C44") (pin "1") (pinfunction "1_1") (pintype "passive"))
      (node (ref "C45") (pin "1") (pinfunction "1_1") (pintype "passive"))
      (node (ref "C49") (pin "2") (pinfunction "2_2") (pintype "passive"))
      (node (ref "C50") (pin "2") (pinfunction "2_2") (pintype "passive"))
      (node (ref "C7") (pin "2") (pinfunction "2_2") (pintype "passive"))
      (node (ref "D2") (pin "1") (pinfunction "A1_1") (pintype "passive"))
      (node (ref "D3") (pin "1") (pinfunction "A1_1") (pintype "passive"))
      (node (ref "FB3") (pin "1") (pinfunction "1_1") (pintype "passive"))
      (node (ref "IC4") (pin "2") (pinfunction "GND_2") (pintype "bidirectional"))
      (node (ref "L3") (pin "1") (pinfunction "1_1") (pintype "passive"))
      (node (ref "L5") (pin "1") (pinfunction "1_1") (pintype "passive"))
      (node (ref "L6") (pin "1") (pinfunction "1_1") (pintype "passive"))
      (node (ref "L7") (pin "1") (pinfunction "1_1") (pintype "passive"))
      (node (ref "R15") (pin "1") (pinfunction "1_1") (pintype "passive"))
      (node (ref "R16") (pin "1") (pinfunction "1_1") (pintype "passive"))
      (node (ref "U$6") (pin "8") (pinfunction "GND_8") (pintype "bidirectional"))
    )
    (net (code "18") (name "/AVR->K20") (class "Default")
      (node (ref "IC1") (pin "2") (pinfunction "PTE1_2") (pintype "bidirectional"))
      (node (ref "U2") (pin "31") (pinfunction "PD1(TXD)_31") (pintype "bidirectional"))
    )
    (net (code "19") (name "/AVR_MISO") (class "Default")
      (node (ref "AVR_ISP") (pin "1") (pinfunction "1_1") (pintype "bidirectional"))
      (node (ref "U2") (pin "16") (pinfunction "PB4(MISO)_16") (pintype "bidirectional"))
    )
    (net (code "20") (name "/AVR_MOSI") (class "Default")
      (node (ref "AVR_ISP") (pin "4") (pinfunction "4_4") (pintype "bidirectional"))
      (node (ref "U2") (pin "15") (pinfunction "PB3(MOSI/OC2)_15") (pintype "bidirectional"))
    )
    (net (code "21") (name "/AVR_RESET") (class "Default")
      (node (ref "AVR_ISP") (pin "5") (pinfunction "5_5") (pintype "bidirectional"))
      (node (ref "R9") (pin "1") (pinfunction "1_1") (pintype "bidirectional"))
      (node (ref "U2") (pin "29") (pinfunction "PC6(/RESET)_29") (pintype "bidirectional"))
    )
    (net (code "22") (name "/AVR_SCK") (class "Default")
      (node (ref "AVR_ISP") (pin "3") (pinfunction "3_3") (pintype "bidirectional"))
      (node (ref "U2") (pin "17") (pinfunction "PB5(SCK)_17") (pintype "bidirectional"))
    )
    (net (code "23") (name "/B0_GPIO") (class "Default")
      (node (ref "IC1") (pin "35") (pinfunction "PTB0_35") (pintype "bidirectional"))
      (node (ref "X4") (pin "3") (pinfunction "1_3") (pintype "passive"))
    )
    (net (code "24") (name "/B1_GPIO") (class "Default")
      (node (ref "IC1") (pin "36") (pinfunction "PTB1_36") (pintype "bidirectional"))
      (node (ref "X4") (pin "4") (pinfunction "1_4") (pintype "passive"))
    )
    (net (code "25") (name "/B19_GPIO") (class "Default")
      (node (ref "IC1") (pin "42") (pinfunction "PTB19_42") (pintype "bidirectional"))
      (node (ref "X4") (pin "5") (pinfunction "1_5") (pintype "passive"))
    )
    (net (code "26") (name "/BACKLIGHT") (class "Default")
      (node (ref "IC1") (pin "43") (pinfunction "PTC0_43") (pintype "bidirectional"))
      (node (ref "R19") (pin "2") (pinfunction "2_2") (pintype "bidirectional"))
    )
    (net (code "27") (name "/BLUE") (class "Default")
      (node (ref "R6") (pin "2") (pinfunction "2_2") (pintype "bidirectional"))
      (node (ref "U4") (pin "14") (pinfunction "PTB2/IRQ_7/UART0_TX/UART0_RX_14") (pintype "bidirectional"))
    )
    (net (code "28") (name "/BUTTON1") (class "Default")
      (node (ref "IC3") (pin "11") (pinfunction "A_11") (pintype "input"))
      (node (ref "R23") (pin "4") (pinfunction "1_4") (pintype "passive"))
      (node (ref "S1") (pin "1") (pinfunction "S_1") (pintype "passive"))
      (node (ref "S1") (pin "2") (pinfunction "S1_2") (pintype "passive"))
    )
    (net (code "29") (name "/BUTTON2") (class "Default")
      (node (ref "IC3") (pin "12") (pinfunction "B_12") (pintype "input"))
      (node (ref "R23") (pin "3") (pinfunction "1_3") (pintype "passive"))
      (node (ref "S2") (pin "1") (pinfunction "S_1") (pintype "passive"))
      (node (ref "S2") (pin "2") (pinfunction "S1_2") (pintype "passive"))
    )
    (net (code "30") (name "/BUTTON3") (class "Default")
      (node (ref "IC3") (pin "13") (pinfunction "C_13") (pintype "input"))
      (node (ref "R23") (pin "2") (pinfunction "1_2") (pintype "passive"))
      (node (ref "S3") (pin "1") (pinfunction "S_1") (pintype "passive"))
      (node (ref "S3") (pin "2") (pinfunction "S1_2") (pintype "passive"))
    )
    (net (code "31") (name "/BUTTON4") (class "Default")
      (node (ref "IC3") (pin "14") (pinfunction "D_14") (pintype "input"))
      (node (ref "R23") (pin "1") (pinfunction "1_1") (pintype "passive"))
      (node (ref "S4") (pin "1") (pinfunction "S_1") (pintype "passive"))
      (node (ref "S4") (pin "2") (pinfunction "S1_2") (pintype "passive"))
    )
    (net (code "32") (name "/BUTTON5") (class "Default")
      (node (ref "IC3") (pin "3") (pinfunction "E_3") (pintype "input"))
      (node (ref "R4") (pin "3") (pinfunction "1_3") (pintype "passive"))
      (node (ref "S5") (pin "1") (pinfunction "S_1") (pintype "passive"))
      (node (ref "S5") (pin "2") (pinfunction "S1_2") (pintype "passive"))
    )
    (net (code "33") (name "/BUTTON6") (class "Default")
      (node (ref "IC3") (pin "4") (pinfunction "F_4") (pintype "input"))
      (node (ref "R4") (pin "2") (pinfunction "1_2") (pintype "passive"))
      (node (ref "S6") (pin "1") (pinfunction "S_1") (pintype "passive"))
      (node (ref "S6") (pin "2") (pinfunction "S1_2") (pintype "passive"))
    )
    (net (code "34") (name "/BUTTON7") (class "Default")
      (node (ref "IC3") (pin "5") (pinfunction "G_5") (pintype "input"))
      (node (ref "R4") (pin "1") (pinfunction "1_1") (pintype "passive"))
      (node (ref "S7") (pin "1") (pinfunction "S_1") (pintype "passive"))
      (node (ref "S7") (pin "2") (pinfunction "S1_2") (pintype "passive"))
    )
    (net (code "35") (name "/BUTTON8_GPIO") (class "Default")
      (node (ref "IC3") (pin "6") (pinfunction "H_6") (pintype "input"))
    )
    (net (code "36") (name "/BUTTON_CLK") (class "Default")
      (node (ref "IC3") (pin "2") (pinfunction "CLK_2") (pintype "input"))
      (node (ref "U2") (pin "1") (pinfunction "PD3(INT1)_1") (pintype "bidirectional"))
    )
    (net (code "37") (name "/BUTTON_DAT") (class "Default")
      (node (ref "IC3") (pin "9") (pinfunction "QH_9") (pintype "output"))
      (node (ref "U2") (pin "2") (pinfunction "PD4(XCK/T0)_2") (pintype "bidirectional"))
    )
    (net (code "38") (name "/BUTTON_LOAD") (class "Default")
      (node (ref "IC3") (pin "1") (pinfunction "SH/~{LD}_1") (pintype "input"))
      (node (ref "U2") (pin "32") (pinfunction "PD2(INT0)_32") (pintype "bidirectional"))
    )
    (net (code "39") (name "/C9_GPIO") (class "Default")
      (node (ref "IC1") (pin "54") (pinfunction "PTC9_54") (pintype "bidirectional"))
      (node (ref "X4") (pin "6") (pinfunction "1_6") (pintype "passive"))
    )
    (net (code "40") (name "/C10_GPIO") (class "Default")
      (node (ref "IC1") (pin "55") (pinfunction "PTC10_55") (pintype "bidirectional"))
      (node (ref "X4") (pin "7") (pinfunction "1_7") (pintype "passive"))
    )
    (net (code "41") (name "/C11_GPIO") (class "Default")
      (node (ref "IC1") (pin "56") (pinfunction "PTC11_56") (pintype "bidirectional"))
      (node (ref "X4") (pin "8") (pinfunction "1_8") (pintype "passive"))
    )
    (net (code "42") (name "/D0_GPIO") (class "Default")
      (node (ref "IC1") (pin "57") (pinfunction "PTD0_57") (pintype "bidirectional"))
      (node (ref "X4") (pin "9") (pinfunction "1_9") (pintype "passive"))
    )
    (net (code "43") (name "/D1~{}") (class "Default")
      (node (ref "IC1") (pin "58") (pinfunction "PTD1_58") (pintype "bidirectional"))
    )
    (net (code "44") (name "/D7_GPIO") (class "Default")
      (node (ref "IC1") (pin "64") (pinfunction "PTD7_64") (pintype "bidirectional"))
      (node (ref "X4") (pin "10") (pinfunction "1_10") (pintype "passive"))
    )
    (net (code "45") (name "/DISP_CS") (class "Default")
      (node (ref "IC1") (pin "49") (pinfunction "PTC4_49") (pintype "bidirectional"))
      (node (ref "U$1") (pin "38") (pinfunction "CSX_38") (pintype "input"))
    )
    (net (code "46") (name "/DISP_DC") (class "Default")
      (node (ref "IC1") (pin "46") (pinfunction "PTC3_46") (pintype "bidirectional"))
      (node (ref "U$1") (pin "36") (pinfunction "WRX(D/CX)_36") (pintype "input"))
    )
    (net (code "47") (name "/DISP_RESET") (class "Default")
      (node (ref "IC1") (pin "63") (pinfunction "PTD6_63") (pintype "bidirectional"))
      (node (ref "U$1") (pin "10") (pinfunction "RESET_10") (pintype "input"))
    )
    (net (code "48") (name "/DISP_X+") (class "Default")
      (node (ref "U$1") (pin "44") (pinfunction "X+_44") (pintype "output"))
      (node (ref "U2") (pin "23") (pinfunction "PC0(ADC0)_23") (pintype "bidirectional"))
    )
    (net (code "49") (name "/DISP_X-") (class "Default")
      (node (ref "U$1") (pin "46") (pinfunction "X-_46") (pintype "output"))
      (node (ref "U2") (pin "24") (pinfunction "PC1(ADC1)_24") (pintype "bidirectional"))
    )
    (net (code "50") (name "/DISP_Y+") (class "Default")
      (node (ref "U$1") (pin "45") (pinfunction "Y+_45") (pintype "output"))
      (node (ref "U2") (pin "25") (pinfunction "PC2(ADC2)_25") (pintype "bidirectional"))
    )
    (net (code "51") (name "/DISP_Y-") (class "Default")
      (node (ref "U$1") (pin "47") (pinfunction "Y-_47") (pintype "output"))
      (node (ref "U2") (pin "26") (pinfunction "PC3(ADC3)_26") (pintype "bidirectional"))
    )
    (net (code "52") (name "/ENC1_A") (class "Default")
      (node (ref "SW2") (pin "A") (pinfunction "A_A") (pintype "passive"))
      (node (ref "U2") (pin "14") (pinfunction "PB2(SS/OC1B)_14") (pintype "bidirectional"))
    )
    (net (code "53") (name "/ENC1_B") (class "Default")
      (node (ref "SW2") (pin "B") (pinfunction "B_B") (pintype "passive"))
      (node (ref "U2") (pin "13") (pinfunction "PB1(OC1A)_13") (pintype "bidirectional"))
    )
    (net (code "54") (name "/ENC1_S") (class "Default")
      (node (ref "SW2") (pin "P1") (pinfunction "1_P1") (pintype "passive"))
      (node (ref "U2") (pin "12") (pinfunction "PB0(ICP)_12") (pintype "bidirectional"))
    )
    (net (code "55") (name "/ENC2_A") (class "Default")
      (node (ref "SW1") (pin "A") (pinfunction "A_A") (pintype "passive"))
      (node (ref "U2") (pin "11") (pinfunction "PD7(AIN1)_11") (pintype "bidirectional"))
    )
    (net (code "56") (name "/ENC2_B") (class "Default")
      (node (ref "SW1") (pin "B") (pinfunction "B_B") (pintype "passive"))
      (node (ref "U2") (pin "10") (pinfunction "PD6(AIN0)_10") (pintype "bidirectional"))
    )
    (net (code "57") (name "/ENC2_S") (class "Default")
      (node (ref "SW1") (pin "P1") (pinfunction "1_P1") (pintype "passive"))
      (node (ref "U2") (pin "9") (pinfunction "PD5(T1)_9") (pintype "bidirectional"))
    )
    (net (code "58") (name "/EYE_LED") (class "Default")
      (node (ref "IC1") (pin "61") (pinfunction "PTD4_61") (pintype "bidirectional"))
      (node (ref "R20") (pin "2") (pinfunction "2_2") (pintype "bidirectional"))
    )
    (net (code "59") (name "/GREEN") (class "Default")
      (node (ref "R3") (pin "2") (pinfunction "2_2") (pintype "bidirectional"))
      (node (ref "U4") (pin "13") (pinfunction "PTB1/IRQ_6/UART0_RX/UART0_TX_13") (pintype "bidirectional"))
    )
    (net (code "60") (name "/I2C_SCL") (class "Default")
      (node (ref "IC1") (pin "37") (pinfunction "PTB2_37") (pintype "bidirectional"))
      (node (ref "R1") (pin "1") (pinfunction "1_1") (pintype "bidirectional"))
      (node (ref "U$22") (pin "P$2") (pinfunction "2_P$2") (pintype "bidirectional"))
    )
    (net (code "61") (name "/I2C_SDA") (class "Default")
      (node (ref "IC1") (pin "38") (pinfunction "PTB3_38") (pintype "bidirectional"))
      (node (ref "R18") (pin "1") (pinfunction "1_1") (pintype "bidirectional"))
      (node (ref "U$22") (pin "P$3") (pinfunction "3_P$3") (pintype "bidirectional"))
    )
    (net (code "62") (name "/I2S_BCLK") (class "Default")
      (node (ref "IC1") (pin "41") (pinfunction "PTB18_41") (pintype "bidirectional"))
      (node (ref "U$21") (pin "P$3") (pinfunction "3_P$3") (pintype "bidirectional"))
      (node (ref "U$6") (pin "2") (pinfunction "~{DEM/SCLK}_2") (pintype "bidirectional"))
    )
    (net (code "63") (name "/I2S_DAT") (class "Default")
      (node (ref "IC1") (pin "44") (pinfunction "PTC1_44") (pintype "bidirectional"))
      (node (ref "U$21") (pin "P$4") (pinfunction "4_P$4") (pintype "bidirectional"))
      (node (ref "U$6") (pin "1") (pinfunction "SDIN_1") (pintype "bidirectional"))
    )
    (net (code "64") (name "/I2S_LRC") (class "Default")
      (node (ref "IC1") (pin "45") (pinfunction "PTC2_45") (pintype "bidirectional"))
      (node (ref "U$21") (pin "P$2") (pinfunction "2_P$2") (pintype "bidirectional"))
      (node (ref "U$6") (pin "3") (pinfunction "LRCK_3") (pintype "bidirectional"))
    )
    (net (code "65") (name "/I2S_MCLK") (class "Default")
      (node (ref "IC1") (pin "53") (pinfunction "PTC8_53") (pintype "bidirectional"))
      (node (ref "U$21") (pin "P$1") (pinfunction "1_P$1") (pintype "bidirectional"))
      (node (ref "U$6") (pin "4") (pinfunction "MCLK_4") (pintype "bidirectional"))
    )
    (net (code "66") (name "/INPUTPOWER") (class "Default")
      (node (ref "C16") (pin "+") (pinfunction "1_+") (pintype "bidirectional"))
      (node (ref "C17") (pin "2") (pinfunction "2_2") (pintype "bidirectional"))
      (node (ref "C20") (pin "+") (pinfunction "1_+") (pintype "bidirectional"))
      (node (ref "C29") (pin "2") (pinfunction "2_2") (pintype "bidirectional"))
      (node (ref "C5") (pin "+") (pinfunction "1_+") (pintype "bidirectional"))
      (node (ref "D4") (pin "C") (pinfunction "-_C") (pintype "passive"))
      (node (ref "D5") (pin "C") (pinfunction "-_C") (pintype "passive"))
      (node (ref "IC1") (pin "8") (pinfunction "VREGIN_8") (pintype "bidirectional"))
      (node (ref "IC2") (pin "3") (pinfunction "IN_3") (pintype "input"))
      (node (ref "IC4") (pin "1") (pinfunction "VIN_1") (pintype "bidirectional"))
      (node (ref "IC4") (pin "3") (pinfunction "EN_3") (pintype "bidirectional"))
    )
    (net (code "67") (name "/K20->AVR") (class "Default")
      (node (ref "IC1") (pin "1") (pinfunction "PTE0_1") (pintype "bidirectional"))
      (node (ref "U2") (pin "30") (pinfunction "PD0(RXD)_30") (pintype "bidirectional"))
    )
    (net (code "68") (name "/K20->KL02") (class "Default")
      (node (ref "IC1") (pin "60") (pinfunction "PTD3_60") (pintype "bidirectional"))
      (node (ref "R27") (pin "2") (pinfunction "2_2") (pintype "bidirectional"))
      (node (ref "U4") (pin "18") (pinfunction "PTB4/IRQ_11/I2C0_SDA/UART0_RX_18") (pintype "bidirectional"))
    )
    (net (code "69") (name "/KL02->K20") (class "Default")
      (node (ref "IC1") (pin "59") (pinfunction "PTD2_59") (pintype "bidirectional"))
      (node (ref "R26") (pin "2") (pinfunction "2_2") (pintype "bidirectional"))
      (node (ref "U4") (pin "17") (pinfunction "PTB3/IRQ_10/I2C0_SCL/UART0_TX_17") (pintype "bidirectional"))
    )
    (net (code "70") (name "/LA1") (class "Default")
      (node (ref "U$9") (pin "ANODE") (pinfunction "ANODE_ANODE") (pintype "bidirectional"))
      (node (ref "U4") (pin "2") (pinfunction "PTB7/IRQ_3_2") (pintype "bidirectional"))
    )
    (net (code "71") (name "/LA2") (class "Default")
      (node (ref "U$10") (pin "ANODE") (pinfunction "ANODE_ANODE") (pintype "bidirectional"))
      (node (ref "U4") (pin "9") (pinfunction "PTB10_9") (pintype "bidirectional"))
    )
    (net (code "72") (name "/LA3") (class "Default")
      (node (ref "U$12") (pin "ANODE") (pinfunction "ANODE_ANODE") (pintype "bidirectional"))
      (node (ref "U4") (pin "10") (pinfunction "PTB11_10") (pintype "bidirectional"))
    )
    (net (code "73") (name "/LA4") (class "Default")
      (node (ref "U$13") (pin "ANODE") (pinfunction "ANODE_ANODE") (pintype "bidirectional"))
      (node (ref "U4") (pin "21") (pinfunction "PTB13_21") (pintype "bidirectional"))
    )
    (net (code "74") (name "/LA5") (class "Default")
      (node (ref "U$14") (pin "ANODE") (pinfunction "ANODE_ANODE") (pintype "bidirectional"))
      (node (ref "U4") (pin "7") (pinfunction "PTA5/SPI0_SS_B_7") (pintype "bidirectional"))
    )
    (net (code "75") (name "/LA6") (class "Default")
      (node (ref "U$15") (pin "ANODE") (pinfunction "ANODE_ANODE") (pintype "bidirectional"))
      (node (ref "U4") (pin "8") (pinfunction "PTA6/SPI0_MISO_8") (pintype "bidirectional"))
    )
    (net (code "76") (name "/LA7") (class "Default")
      (node (ref "U$16") (pin "ANODE") (pinfunction "ANODE_ANODE") (pintype "bidirectional"))
      (node (ref "U4") (pin "11") (pinfunction "PTA7/IRQ_4/SPI0_MOSI/SPI0_MISO_11") (pintype "bidirectional"))
    )
    (net (code "77") (name "/LA8") (class "Default")
      (node (ref "U$17") (pin "ANODE") (pinfunction "ANODE_ANODE") (pintype "bidirectional"))
      (node (ref "U4") (pin "15") (pinfunction "PTA8/I2C1_SCL_15") (pintype "bidirectional"))
    )
    (net (code "78") (name "/LA9") (class "Default")
      (node (ref "U$18") (pin "ANODE") (pinfunction "ANODE_ANODE") (pintype "bidirectional"))
      (node (ref "U4") (pin "16") (pinfunction "PTA9/I2C1_SDA_16") (pintype "bidirectional"))
    )
    (net (code "79") (name "/MIDI_IN") (class "Default")
      (node (ref "IC1") (pin "39") (pinfunction "PTB16_39") (pintype "bidirectional"))
      (node (ref "IC5") (pin "5") (pinfunction "COL_5") (pintype "passive"))
      (node (ref "R37") (pin "1") (pinfunction "1_1") (pintype "bidirectional"))
      (node (ref "U1") (pin "9") (pinfunction "4A_9") (pintype "input"))
    )
    (net (code "80") (name "/MIDI_OUT") (class "Default")
      (node (ref "IC1") (pin "40") (pinfunction "PTB17_40") (pintype "bidirectional"))
      (node (ref "U1") (pin "13") (pinfunction "6A_13") (pintype "input"))
    )
    (net (code "81") (name "/MK20_RESET") (class "Default")
      (node (ref "BUTTON1") (pin "1") (pinfunction "A0_1") (pintype "bidirectional"))
      (node (ref "IC1") (pin "34") (pinfunction "RESET_B_34") (pintype "bidirectional"))
      (node (ref "R17") (pin "2") (pinfunction "2_2") (pintype "bidirectional"))
      (node (ref "SWD1") (pin "10") (pinfunction "RESET_10") (pintype "bidirectional"))
    )
    (net (code "82") (name "/N$1") (class "Default")
      (node (ref "R25") (pin "1") (pinfunction "1_1") (pintype "passive"))
      (node (ref "R25") (pin "2") (pinfunction "1_2") (pintype "passive"))
      (node (ref "R25") (pin "3") (pinfunction "1_3") (pintype "passive"))
      (node (ref "R25") (pin "4") (pinfunction "1_4") (pintype "passive"))
      (node (ref "U3") (pin "3") (pinfunction "C_3") (pintype "passive"))
    )
    (net (code "83") (name "/PC4_GPIO") (class "Default")
      (node (ref "U$20") (pin "P$1") (pinfunction "1_P$1") (pintype "bidirectional"))
      (node (ref "U2") (pin "27") (pinfunction "PC4(ADC4/SDA)_27") (pintype "bidirectional"))
    )
    (net (code "84") (name "/PC5_GPIO") (class "Default")
      (node (ref "U$20") (pin "P$2") (pinfunction "2_P$2") (pintype "bidirectional"))
      (node (ref "U2") (pin "28") (pinfunction "PC5(ADC5/SCL)_28") (pintype "bidirectional"))
    )
    (net (code "85") (name "/PTA1") (class "Default")
      (node (ref "SWD2") (pin "10") (pinfunction "RESET_10") (pintype "bidirectional"))
      (node (ref "U4") (pin "23") (pinfunction "PTA1/IRQ_1/LPTMR0_ALT1/RESET_B_23") (pintype "bidirectional"))
    )
    (net (code "86") (name "/PTA3_GPIO") (class "Default")
      (node (ref "U$11") (pin "P$2") (pinfunction "2_P$2") (pintype "bidirectional"))
      (node (ref "U4") (pin "5") (pinfunction "PTA3/EXTAL0/I2C0_SCL/I2C1_SDA_5") (pintype "bidirectional"))
    )
    (net (code "87") (name "/PTA4_GPIO") (class "Default")
      (node (ref "U$11") (pin "P$1") (pinfunction "1_P$1") (pintype "bidirectional"))
      (node (ref "U4") (pin "6") (pinfunction "PTA4/XTAL0/I2C0_SDA/I2C1_SCL_6") (pintype "bidirectional"))
    )
    (net (code "88") (name "/PTA12_GPIO") (class "Default")
      (node (ref "U$11") (pin "P$4") (pinfunction "4_P$4") (pintype "bidirectional"))
      (node (ref "U4") (pin "20") (pinfunction "PTA12/IRQ_13/LPTMR0_ALT2_20") (pintype "bidirectional"))
    )
    (net (code "89") (name "/PTB5_GPIO") (class "Default")
      (node (ref "U$11") (pin "P$5") (pinfunction "5_P$5") (pintype "bidirectional"))
      (node (ref "U4") (pin "19") (pinfunction "PTB5/IRQ_12/NMI_B_19") (pintype "bidirectional"))
    )
    (net (code "90") (name "/PTB6_GPIO") (class "Default")
      (node (ref "U$11") (pin "P$3") (pinfunction "3_P$3") (pintype "bidirectional"))
      (node (ref "U4") (pin "1") (pinfunction "PTB6/IRQ_2/LPTMR0_ALT3_1") (pintype "bidirectional"))
    )
    (net (code "91") (name "/RBLUE") (class "Default")
      (node (ref "R6") (pin "1") (pinfunction "1_1") (pintype "bidirectional"))
      (node (ref "U$10") (pin "B") (pinfunction "B_B") (pintype "bidirectional"))
      (node (ref "U$12") (pin "B") (pinfunction "B_B") (pintype "bidirectional"))
      (node (ref "U$13") (pin "B") (pinfunction "B_B") (pintype "bidirectional"))
      (node (ref "U$14") (pin "B") (pinfunction "B_B") (pintype "bidirectional"))
      (node (ref "U$15") (pin "B") (pinfunction "B_B") (pintype "bidirectional"))
      (node (ref "U$16") (pin "B") (pinfunction "B_B") (pintype "bidirectional"))
      (node (ref "U$17") (pin "B") (pinfunction "B_B") (pintype "bidirectional"))
      (node (ref "U$18") (pin "B") (pinfunction "B_B") (pintype "bidirectional"))
      (node (ref "U$9") (pin "B") (pinfunction "B_B") (pintype "bidirectional"))
    )
    (net (code "92") (name "/RED") (class "Default")
      (node (ref "R2") (pin "2") (pinfunction "2_2") (pintype "bidirectional"))
      (node (ref "U4") (pin "12") (pinfunction "PTB0/IRQ_5/SPI0_SCK_12") (pintype "bidirectional"))
    )
    (net (code "93") (name "/RGREEN") (class "Default")
      (node (ref "R3") (pin "1") (pinfunction "1_1") (pintype "bidirectional"))
      (node (ref "U$10") (pin "G") (pinfunction "G_G") (pintype "bidirectional"))
      (node (ref "U$12") (pin "G") (pinfunction "G_G") (pintype "bidirectional"))
      (node (ref "U$13") (pin "G") (pinfunction "G_G") (pintype "bidirectional"))
      (node (ref "U$14") (pin "G") (pinfunction "G_G") (pintype "bidirectional"))
      (node (ref "U$15") (pin "G") (pinfunction "G_G") (pintype "bidirectional"))
      (node (ref "U$16") (pin "G") (pinfunction "G_G") (pintype "bidirectional"))
      (node (ref "U$17") (pin "G") (pinfunction "G_G") (pintype "bidirectional"))
      (node (ref "U$18") (pin "G") (pinfunction "G_G") (pintype "bidirectional"))
      (node (ref "U$9") (pin "G") (pinfunction "G_G") (pintype "bidirectional"))
    )
    (net (code "94") (name "/RRED") (class "Default")
      (node (ref "R2") (pin "1") (pinfunction "1_1") (pintype "bidirectional"))
      (node (ref "U$10") (pin "R") (pinfunction "R_R") (pintype "bidirectional"))
      (node (ref "U$12") (pin "R") (pinfunction "R_R") (pintype "bidirectional"))
      (node (ref "U$13") (pin "R") (pinfunction "R_R") (pintype "bidirectional"))
      (node (ref "U$14") (pin "R") (pinfunction "R_R") (pintype "bidirectional"))
      (node (ref "U$15") (pin "R") (pinfunction "R_R") (pintype "bidirectional"))
      (node (ref "U$16") (pin "R") (pinfunction "R_R") (pintype "bidirectional"))
      (node (ref "U$17") (pin "R") (pinfunction "R_R") (pintype "bidirectional"))
      (node (ref "U$18") (pin "R") (pinfunction "R_R") (pintype "bidirectional"))
      (node (ref "U$9") (pin "R") (pinfunction "R_R") (pintype "bidirectional"))
    )
    (net (code "95") (name "/SDCARD_CS") (class "Default")
      (node (ref "IC1") (pin "62") (pinfunction "PTD5_62") (pintype "bidirectional"))
      (node (ref "J1") (pin "2") (pinfunction "CS_2") (pintype "bidirectional"))
    )
    (net (code "96") (name "/SERIAL_IN_GPIO") (class "Default")
      (node (ref "IC3") (pin "10") (pinfunction "SER_10") (pintype "input"))
    )
    (net (code "97") (name "/SPI_MISO") (class "Default")
      (node (ref "IC1") (pin "52") (pinfunction "PTC7_52") (pintype "bidirectional"))
      (node (ref "J1") (pin "7") (pinfunction "DO_7") (pintype "bidirectional"))
      (node (ref "U$1") (pin "33") (pinfunction "SDO_33") (pintype "output"))
    )
    (net (code "98") (name "/SPI_MOSI") (class "Default")
      (node (ref "IC1") (pin "51") (pinfunction "PTC6_51") (pintype "bidirectional"))
      (node (ref "J1") (pin "3") (pinfunction "DI_3") (pintype "bidirectional"))
      (node (ref "U$1") (pin "34") (pinfunction "SDI_34") (pintype "input"))
    )
    (net (code "99") (name "/SPI_SCK") (class "Default")
      (node (ref "IC1") (pin "50") (pinfunction "PTC5_50") (pintype "bidirectional"))
      (node (ref "J1") (pin "5") (pinfunction "SCLK_5") (pintype "bidirectional"))
      (node (ref "U$1") (pin "37") (pinfunction "D/CX(SCL)_37") (pintype "input"))
    )
    (net (code "100") (name "/USBMINUS") (class "Default")
      (node (ref "IC1") (pin "6") (pinfunction "USB0_DM_6") (pintype "bidirectional"))
      (node (ref "R31") (pin "2") (pinfunction "2_2") (pintype "bidirectional"))
    )
    (net (code "101") (name "/USBPLUS") (class "Default")
      (node (ref "IC1") (pin "5") (pinfunction "USB0_DP_5") (pintype "bidirectional"))
      (node (ref "R32") (pin "2") (pinfunction "2_2") (pintype "bidirectional"))
    )
    (net (code "102") (name "/USB_N") (class "Default")
      (node (ref "J2") (pin "3") (pinfunction "DP_3") (pintype "bidirectional"))
      (node (ref "R32") (pin "1") (pinfunction "1_1") (pintype "bidirectional"))
      (node (ref "X1") (pin "2") (pinfunction "D-_2") (pintype "bidirectional"))
    )
    (net (code "103") (name "/USB_P") (class "Default")
      (node (ref "J2") (pin "2") (pinfunction "DM_2") (pintype "bidirectional"))
      (node (ref "R31") (pin "1") (pinfunction "1_1") (pintype "bidirectional"))
      (node (ref "X1") (pin "3") (pinfunction "D+_3") (pintype "bidirectional"))
    )
    (net (code "104") (name "/VUSB") (class "Default")
      (node (ref "J2") (pin "1") (pinfunction "VCC_1") (pintype "bidirectional"))
      (node (ref "L4") (pin "1") (pinfunction "1_1") (pintype "passive"))
      (node (ref "X1") (pin "1") (pinfunction "VBUS_1") (pintype "power_in"))
    )
    (net (code "105") (name "3.3V") (class "Default")
      (node (ref "AVR_ISP") (pin "2") (pinfunction "2_2") (pintype "bidirectional"))
      (node (ref "C1") (pin "2") (pinfunction "2_2") (pintype "bidirectional"))
      (node (ref "C15") (pin "+") (pinfunction "1_+") (pintype "bidirectional"))
      (node (ref "C18") (pin "2") (pinfunction "2_2") (pintype "bidirectional"))
      (node (ref "C2") (pin "2") (pinfunction "2_2") (pintype "bidirectional"))
      (node (ref "C25") (pin "2") (pinfunction "2_2") (pintype "bidirectional"))
      (node (ref "C3") (pin "2") (pinfunction "2_2") (pintype "bidirectional"))
      (node (ref "C33") (pin "2") (pinfunction "2_2") (pintype "bidirectional"))
      (node (ref "C34") (pin "2") (pinfunction "2_2") (pintype "bidirectional"))
      (node (ref "C35") (pin "2") (pinfunction "2_2") (pintype "bidirectional"))
      (node (ref "C36") (pin "2") (pinfunction "2_2") (pintype "bidirectional"))
      (node (ref "C37") (pin "2") (pinfunction "2_2") (pintype "bidirectional"))
      (node (ref "C4") (pin "2") (pinfunction "2_2") (pintype "bidirectional"))
      (node (ref "C40") (pin "2") (pinfunction "2_2") (pintype "bidirectional"))
      (node (ref "C41") (pin "2") (pinfunction "2_2") (pintype "bidirectional"))
      (node (ref "C42") (pin "2") (pinfunction "2_2") (pintype "bidirectional"))
      (node (ref "C6") (pin "2") (pinfunction "2_2") (pintype "bidirectional"))
      (node (ref "C8") (pin "2") (pinfunction "2_2") (pintype "bidirectional"))
      (node (ref "C9") (pin "2") (pinfunction "2_2") (pintype "bidirectional"))
      (node (ref "IC1") (pin "21") (pinfunction "VBAT_21") (pintype "bidirectional"))
      (node (ref "IC1") (pin "3") (pinfunction "VDD_3") (pintype "bidirectional"))
      (node (ref "IC1") (pin "30") (pinfunction "VDD_30") (pintype "bidirectional"))
      (node (ref "IC1") (pin "48") (pinfunction "VDD_48") (pintype "bidirectional"))
      (node (ref "IC2") (pin "2") (pinfunction "OUT_2") (pintype "passive"))
      (node (ref "IC2") (pin "4") (pinfunction "OUT_4") (pintype "passive"))
      (node (ref "IC3") (pin "16") (pinfunction "VCC_16") (pintype "power_in"))
      (node (ref "J1") (pin "4") (pinfunction "VDD_4") (pintype "bidirectional"))
      (node (ref "JP6") (pin "1") (pinfunction "1_1") (pintype "passive"))
      (node (ref "L2") (pin "2") (pinfunction "2_2") (pintype "passive"))
      (node (ref "R1") (pin "2") (pinfunction "2_2") (pintype "bidirectional"))
      (node (ref "R11") (pin "1") (pinfunction "1_1") (pintype "bidirectional"))
      (node (ref "R14") (pin "2") (pinfunction "2_2") (pintype "bidirectional"))
      (node (ref "R17") (pin "1") (pinfunction "1_1") (pintype "bidirectional"))
      (node (ref "R18") (pin "2") (pinfunction "2_2") (pintype "bidirectional"))
      (node (ref "R22") (pin "1") (pinfunction "1_1") (pintype "bidirectional"))
      (node (ref "R23") (pin "5") (pinfunction "2_5") (pintype "passive"))
      (node (ref "R23") (pin "6") (pinfunction "2_6") (pintype "passive"))
      (node (ref "R23") (pin "7") (pinfunction "2_7") (pintype "passive"))
      (node (ref "R23") (pin "8") (pinfunction "2_8") (pintype "passive"))
      (node (ref "R24") (pin "2") (pinfunction "2_2") (pintype "bidirectional"))
      (node (ref "R26") (pin "1") (pinfunction "1_1") (pintype "bidirectional"))
      (node (ref "R27") (pin "1") (pinfunction "1_1") (pintype "bidirectional"))
      (node (ref "R37") (pin "2") (pinfunction "2_2") (pintype "bidirectional"))
      (node (ref "R4") (pin "6") (pinfunction "2_6") (pintype "passive"))
      (node (ref "R4") (pin "7") (pinfunction "2_7") (pintype "passive"))
      (node (ref "R4") (pin "8") (pinfunction "2_8") (pintype "passive"))
      (node (ref "R5") (pin "2") (pinfunction "2_2") (pintype "bidirectional"))
      (node (ref "R7") (pin "2") (pinfunction "2_2") (pintype "bidirectional"))
      (node (ref "R8") (pin "2") (pinfunction "2_2") (pintype "bidirectional"))
      (node (ref "R9") (pin "2") (pinfunction "2_2") (pintype "bidirectional"))
      (node (ref "SWD1") (pin "1") (pinfunction "VCC_1") (pintype "bidirectional"))
      (node (ref "SWD2") (pin "1") (pinfunction "VCC_1") (pintype "bidirectional"))
      (node (ref "U$1") (pin "35") (pinfunction "RD_35") (pintype "input"))
      (node (ref "U$1") (pin "40") (pinfunction "VDDI_40") (pintype "power_in"))
      (node (ref "U$1") (pin "41") (pinfunction "VDDI2_41") (pintype "power_in"))
      (node (ref "U$1") (pin "42") (pinfunction "VCI_42") (pintype "power_in"))
      (node (ref "U$1") (pin "7") (pinfunction "IM1_7") (pintype "input"))
      (node (ref "U$1") (pin "8") (pinfunction "IM2_8") (pintype "input"))
      (node (ref "U$1") (pin "9") (pinfunction "IM3_9") (pintype "input"))
      (node (ref "U$22") (pin "P$1") (pinfunction "1_P$1") (pintype "bidirectional"))
      (node (ref "U1") (pin "14") (pinfunction "VCC_14") (pintype "power_in"))
      (node (ref "U2") (pin "18") (pinfunction "AVCC_18") (pintype "bidirectional"))
      (node (ref "U2") (pin "20") (pinfunction "AREF_20") (pintype "bidirectional"))
      (node (ref "U2") (pin "4") (pinfunction "VCC_4") (pintype "bidirectional"))
      (node (ref "U2") (pin "6") (pinfunction "VCC_6") (pintype "bidirectional"))
      (node (ref "U3") (pin "2") (pinfunction "E_2") (pintype "passive"))
      (node (ref "U4") (pin "3") (pinfunction "VDD_VREFH_3") (pintype "power_in"))
    )
    (net (code "106") (name "DGND") (class "Default")
      (node (ref "AVR_ISP") (pin "6") (pinfunction "6_6") (pintype "bidirectional"))
      (node (ref "BUTTON1") (pin "2") (pinfunction "B0_2") (pintype "bidirectional"))
      (node (ref "C1") (pin "1") (pinfunction "1_1") (pintype "bidirectional"))
      (node (ref "C15") (pin "-") (pinfunction "2_-") (pintype "bidirectional"))
      (node (ref "C16") (pin "-") (pinfunction "2_-") (pintype "bidirectional"))
      (node (ref "C17") (pin "1") (pinfunction "1_1") (pintype "bidirectional"))
      (node (ref "C18") (pin "1") (pinfunction "1_1") (pintype "bidirectional"))
      (node (ref "C2") (pin "1") (pinfunction "1_1") (pintype "bidirectional"))
      (node (ref "C23") (pin "1") (pinfunction "1_1") (pintype "bidirectional"))
      (node (ref "C24") (pin "1") (pinfunction "1_1") (pintype "bidirectional"))
      (node (ref "C25") (pin "1") (pinfunction "1_1") (pintype "bidirectional"))
      (node (ref "C3") (pin "1") (pinfunction "1_1") (pintype "bidirectional"))
      (node (ref "C33") (pin "1") (pinfunction "1_1") (pintype "bidirectional"))
      (node (ref "C34") (pin "1") (pinfunction "1_1") (pintype "bidirectional"))
      (node (ref "C35") (pin "1") (pinfunction "1_1") (pintype "bidirectional"))
      (node (ref "C36") (pin "1") (pinfunction "1_1") (pintype "bidirectional"))
      (node (ref "C37") (pin "1") (pinfunction "1_1") (pintype "bidirectional"))
      (node (ref "C38") (pin "1") (pinfunction "1_1") (pintype "bidirectional"))
      (node (ref "C39") (pin "1") (pinfunction "1_1") (pintype "bidirectional"))
      (node (ref "C4") (pin "1") (pinfunction "1_1") (pintype "bidirectional"))
      (node (ref "C40") (pin "1") (pinfunction "1_1") (pintype "bidirectional"))
      (node (ref "C41") (pin "1") (pinfunction "1_1") (pintype "bidirectional"))
      (node (ref "C42") (pin "1") (pinfunction "1_1") (pintype "bidirectional"))
      (node (ref "C5") (pin "-") (pinfunction "2_-") (pintype "bidirectional"))
      (node (ref "C6") (pin "1") (pinfunction "1_1") (pintype "bidirectional"))
      (node (ref "C8") (pin "1") (pinfunction "1_1") (pintype "bidirectional"))
      (node (ref "C9") (pin "1") (pinfunction "1_1") (pintype "bidirectional"))
      (node (ref "IC1") (pin "15") (pinfunction "VREFL_15") (pintype "bidirectional"))
      (node (ref "IC1") (pin "16") (pinfunction "VSSA_16") (pintype "bidirectional"))
      (node (ref "IC1") (pin "31") (pinfunction "VSS_31") (pintype "bidirectional"))
      (node (ref "IC1") (pin "4") (pinfunction "VSS_4") (pintype "bidirectional"))
      (node (ref "IC1") (pin "47") (pinfunction "VSS_47") (pintype "bidirectional"))
      (node (ref "IC2") (pin "1") (pinfunction "ADJ_1") (pintype "input"))
      (node (ref "IC3") (pin "15") (pinfunction "INH_15") (pintype "input"))
      (node (ref "IC3") (pin "8") (pinfunction "GND_8") (pintype "power_in"))
      (node (ref "IC5") (pin "4") (pinfunction "EMI_4") (pintype "passive"))
      (node (ref "IC6") (pin "1") (pinfunction "ADJ_1") (pintype "input"))
      (node (ref "J1") (pin "6") (pinfunction "VSS_6") (pintype "bidirectional"))
      (node (ref "J1") (pin "G1") (pinfunction "G1_G1") (pintype "bidirectional"))
      (node (ref "J1") (pin "G2") (pinfunction "G2_G2") (pintype "bidirectional"))
      (node (ref "J1") (pin "G3") (pinfunction "G3_G3") (pintype "bidirectional"))
      (node (ref "J1") (pin "G4") (pinfunction "G4_G4") (pintype "bidirectional"))
      (node (ref "J2") (pin "5") (pinfunction "GND_5") (pintype "bidirectional"))
      (node (ref "JP6") (pin "2") (pinfunction "2_2") (pintype "passive"))
      (node (ref "L1") (pin "1") (pinfunction "1_1") (pintype "passive"))
      (node (ref "L3") (pin "2") (pinfunction "2_2") (pintype "passive"))
      (node (ref "L5") (pin "2") (pinfunction "2_2") (pintype "passive"))
      (node (ref "L6") (pin "2") (pinfunction "2_2") (pintype "passive"))
      (node (ref "L7") (pin "2") (pinfunction "2_2") (pintype "passive"))
      (node (ref "LED_EYE") (pin "C") (pinfunction "C_C") (pintype "passive"))
      (node (ref "LED_PWR") (pin "C") (pinfunction "C_C") (pintype "passive"))
      (node (ref "PORT_MIDI-OUT") (pin "2") (pinfunction "2_2") (pintype "passive"))
      (node (ref "PORT_MIDI-OUT") (pin "PE") (pinfunction "MT_PE") (pintype "passive"))
      (node (ref "PORT_MIDI-OUT") (pin "PE1") (pinfunction "MT_PE1") (pintype "passive"))
      (node (ref "PORT_MIDI-OUT") (pin "PE2") (pinfunction "MT_PE2") (pintype "passive"))
      (node (ref "PORT_MIDI-OUT") (pin "PE@") (pinfunction "MT_PE@") (pintype "passive"))
      (node (ref "PORT_MIDI-THROUGH") (pin "2") (pinfunction "2_2") (pintype "passive"))
      (node (ref "PORT_MIDI-THROUGH") (pin "PE") (pinfunction "MT_PE") (pintype "passive"))
      (node (ref "PORT_MIDI-THROUGH") (pin "PE1") (pinfunction "MT_PE1") (pintype "passive"))
      (node (ref "PORT_MIDI-THROUGH") (pin "PE2") (pinfunction "MT_PE2") (pintype "passive"))
      (node (ref "PORT_MIDI-THROUGH") (pin "PE@") (pinfunction "MT_PE@") (pintype "passive"))
      (node (ref "S1") (pin "3") (pinfunction "P_3") (pintype "passive"))
      (node (ref "S1") (pin "4") (pinfunction "P1_4") (pintype "passive"))
      (node (ref "S2") (pin "3") (pinfunction "P_3") (pintype "passive"))
      (node (ref "S2") (pin "4") (pinfunction "P1_4") (pintype "passive"))
      (node (ref "S3") (pin "3") (pinfunction "P_3") (pintype "passive"))
      (node (ref "S3") (pin "4") (pinfunction "P1_4") (pintype "passive"))
      (node (ref "S4") (pin "3") (pinfunction "P_3") (pintype "passive"))
      (node (ref "S4") (pin "4") (pinfunction "P1_4") (pintype "passive"))
      (node (ref "S5") (pin "3") (pinfunction "P_3") (pintype "passive"))
      (node (ref "S5") (pin "4") (pinfunction "P1_4") (pintype "passive"))
      (node (ref "S6") (pin "3") (pinfunction "P_3") (pintype "passive"))
      (node (ref "S6") (pin "4") (pinfunction "P1_4") (pintype "passive"))
      (node (ref "S7") (pin "3") (pinfunction "P_3") (pintype "passive"))
      (node (ref "S7") (pin "4") (pinfunction "P1_4") (pintype "passive"))
      (node (ref "SW1") (pin "C") (pinfunction "C_C") (pintype "passive"))
      (node (ref "SW1") (pin "P2") (pinfunction "2_P2") (pintype "passive"))
      (node (ref "SW2") (pin "C") (pinfunction "C_C") (pintype "passive"))
      (node (ref "SW2") (pin "P2") (pinfunction "2_P2") (pintype "passive"))
      (node (ref "SWD1") (pin "3") (pinfunction "GND1_3") (pintype "bidirectional"))
      (node (ref "SWD1") (pin "5") (pinfunction "GND2_5") (pintype "bidirectional"))
      (node (ref "SWD2") (pin "3") (pinfunction "GND1_3") (pintype "bidirectional"))
      (node (ref "SWD2") (pin "5") (pinfunction "GND2_5") (pintype "bidirectional"))
      (node (ref "U$1") (pin "1") (pinfunction "LEDK_1") (pintype "power_in"))
      (node (ref "U$1") (pin "11") (pinfunction "VSYNC_11") (pintype "input"))
      (node (ref "U$1") (pin "12") (pinfunction "HSYNC_12") (pintype "input"))
      (node (ref "U$1") (pin "13") (pinfunction "DOTCLK_13") (pintype "input"))
      (node (ref "U$1") (pin "14") (pinfunction "DE_14") (pintype "bidirectional"))
      (node (ref "U$1") (pin "15") (pinfunction "DB17_15") (pintype "bidirectional"))
      (node (ref "U$1") (pin "16") (pinfunction "DB16_16") (pintype "bidirectional"))
      (node (ref "U$1") (pin "17") (pinfunction "DB15_17") (pintype "bidirectional"))
      (node (ref "U$1") (pin "18") (pinfunction "DB14_18") (pintype "bidirectional"))
      (node (ref "U$1") (pin "19") (pinfunction "DB13_19") (pintype "bidirectional"))
      (node (ref "U$1") (pin "20") (pinfunction "DB12_20") (pintype "bidirectional"))
      (node (ref "U$1") (pin "21") (pinfunction "DB11_21") (pintype "bidirectional"))
      (node (ref "U$1") (pin "22") (pinfunction "DB10_22") (pintype "bidirectional"))
      (node (ref "U$1") (pin "23") (pinfunction "DB9_23") (pintype "bidirectional"))
      (node (ref "U$1") (pin "24") (pinfunction "DB8_24") (pintype "bidirectional"))
      (node (ref "U$1") (pin "25") (pinfunction "DB7_25") (pintype "bidirectional"))
      (node (ref "U$1") (pin "26") (pinfunction "DB6_26") (pintype "bidirectional"))
      (node (ref "U$1") (pin "27") (pinfunction "DB5_27") (pintype "bidirectional"))
      (node (ref "U$1") (pin "28") (pinfunction "DB4_28") (pintype "bidirectional"))
      (node (ref "U$1") (pin "29") (pinfunction "DB3_29") (pintype "bidirectional"))
      (node (ref "U$1") (pin "30") (pinfunction "DB2_30") (pintype "bidirectional"))
      (node (ref "U$1") (pin "31") (pinfunction "DB1_31") (pintype "bidirectional"))
      (node (ref "U$1") (pin "32") (pinfunction "DB0_32") (pintype "bidirectional"))
      (node (ref "U$1") (pin "43") (pinfunction "GND_43") (pintype "power_in"))
      (node (ref "U$1") (pin "48") (pinfunction "GND2_48") (pintype "power_in"))
      (node (ref "U$1") (pin "49") (pinfunction "GND3_49") (pintype "power_in"))
      (node (ref "U$1") (pin "50") (pinfunction "GND4_50") (pintype "power_in"))
      (node (ref "U$1") (pin "6") (pinfunction "IM0_6") (pintype "input"))
      (node (ref "U$22") (pin "P$4") (pinfunction "4_P$4") (pintype "bidirectional"))
      (node (ref "U$7") (pin "RING") (pinfunction "RING_RING") (pintype "bidirectional"))
      (node (ref "U$7") (pin "RING_SW") (pinfunction "RING_SW_RING_SW") (pintype "bidirectional"))
      (node (ref "U1") (pin "1") (pinfunction "1A_1") (pintype "input"))
      (node (ref "U1") (pin "3") (pinfunction "2A_3") (pintype "input"))
      (node (ref "U1") (pin "7") (pinfunction "GND_7") (pintype "passive"))
      (node (ref "U2") (pin "21") (pinfunction "GND_21") (pintype "bidirectional"))
      (node (ref "U2") (pin "3") (pinfunction "GND_3") (pintype "bidirectional"))
      (node (ref "U2") (pin "5") (pinfunction "GND_5") (pintype "bidirectional"))
      (node (ref "U4") (pin "25") (pinfunction "E_PAD_25") (pintype "passive"))
      (node (ref "U4") (pin "4") (pinfunction "VREFL_VSS_4") (pintype "passive"))
      (node (ref "X1") (pin "4") (pinfunction "GND_4") (pintype "power_in"))
    )
    (net (code "107") (name "Net-(C11-1)") (class "Default")
      (node (ref "C11") (pin "+") (pinfunction "1_+") (pintype "bidirectional"))
      (node (ref "D3") (pin "3") (pinfunction "C1A2_3") (pintype "passive"))
      (node (ref "U$6") (pin "10") (pinfunction "AOUTR_10") (pintype "bidirectional"))
    )
    (net (code "108") (name "Net-(C11-2)") (class "Default")
      (node (ref "C11") (pin "-") (pinfunction "2_-") (pintype "bidirectional"))
      (node (ref "R13") (pin "1") (pinfunction "1_1") (pintype "passive"))
      (node (ref "R15") (pin "2") (pinfunction "2_2") (pintype "passive"))
    )
    (net (code "109") (name "Net-(C12-1)") (class "Default")
      (node (ref "C12") (pin "+") (pinfunction "1_+") (pintype "bidirectional"))
      (node (ref "D2") (pin "3") (pinfunction "C1A2_3") (pintype "passive"))
      (node (ref "U$6") (pin "7") (pinfunction "AOUTL_7") (pintype "bidirectional"))
    )
    (net (code "110") (name "Net-(C12-2)") (class "Default")
      (node (ref "C12") (pin "-") (pinfunction "2_-") (pintype "bidirectional"))
      (node (ref "R12") (pin "1") (pinfunction "1_1") (pintype "passive"))
      (node (ref "R16") (pin "2") (pinfunction "2_2") (pintype "passive"))
    )
    (net (code "111") (name "Net-(C13-1)") (class "Default")
      (node (ref "C13") (pin "+") (pinfunction "1_+") (pintype "bidirectional"))
      (node (ref "C49") (pin "1") (pinfunction "1_1") (pintype "passive"))
      (node (ref "U$6") (pin "5") (pinfunction "VQ_5") (pintype "bidirectional"))
    )
    (net (code "112") (name "Net-(C44-Pad2)") (class "Default")
      (node (ref "C44") (pin "2") (pinfunction "2_2") (pintype "passive"))
      (node (ref "FB2") (pin "1") (pinfunction "1_1") (pintype "passive"))
      (node (ref "R13") (pin "2") (pinfunction "2_2") (pintype "passive"))
    )
    (net (code "113") (name "Net-(C45-Pad2)") (class "Default")
      (node (ref "C45") (pin "2") (pinfunction "2_2") (pintype "passive"))
      (node (ref "FB1") (pin "1") (pinfunction "1_1") (pintype "passive"))
      (node (ref "R12") (pin "2") (pinfunction "2_2") (pintype "passive"))
    )
    (net (code "114") (name "Net-(D1-+)") (class "Default")
      (node (ref "D1") (pin "A") (pinfunction "+_A") (pintype "passive"))
      (node (ref "IC5") (pin "2") (pinfunction "C_2") (pintype "passive"))
      (node (ref "PORT_MIDI-IN") (pin "5") (pinfunction "5_5") (pintype "passive"))
    )
    (net (code "115") (name "Net-(D1--)") (class "Default")
      (node (ref "D1") (pin "C") (pinfunction "-_C") (pintype "passive"))
      (node (ref "IC5") (pin "1") (pinfunction "A_1") (pintype "passive"))
      (node (ref "R38") (pin "1") (pinfunction "1_1") (pintype "bidirectional"))
    )
    (net (code "116") (name "Net-(D4-+)") (class "Default")
      (node (ref "D4") (pin "A") (pinfunction "+_A") (pintype "passive"))
      (node (ref "IC6") (pin "2") (pinfunction "OUT_2") (pintype "passive"))
      (node (ref "IC6") (pin "4") (pinfunction "OUT_4") (pintype "passive"))
    )
    (net (code "117") (name "Net-(IC1-PTA18)") (class "Default")
      (node (ref "C23") (pin "2") (pinfunction "2_2") (pintype "bidirectional"))
      (node (ref "IC1") (pin "32") (pinfunction "PTA18_32") (pintype "bidirectional"))
      (node (ref "X2") (pin "2") (pinfunction "2_2") (pintype "passive"))
    )
    (net (code "118") (name "Net-(IC1-PTA19)") (class "Default")
      (node (ref "C24") (pin "2") (pinfunction "2_2") (pintype "bidirectional"))
      (node (ref "IC1") (pin "33") (pinfunction "PTA19_33") (pintype "bidirectional"))
      (node (ref "X2") (pin "1") (pinfunction "1_1") (pintype "passive"))
    )
    (net (code "119") (name "Net-(IC1-VDDA)") (class "Default")
      (node (ref "IC1") (pin "13") (pinfunction "VDDA_13") (pintype "bidirectional"))
      (node (ref "IC1") (pin "14") (pinfunction "VREFH_14") (pintype "bidirectional"))
      (node (ref "L2") (pin "1") (pinfunction "1_1") (pintype "passive"))
    )
    (net (code "120") (name "Net-(IC4-BYP)") (class "Default")
      (node (ref "C32") (pin "2") (pinfunction "2_2") (pintype "bidirectional"))
      (node (ref "IC4") (pin "4") (pinfunction "BYP_4") (pintype "bidirectional"))
    )
    (net (code "121") (name "Net-(IC5-BAS)") (class "Default")
      (node (ref "IC5") (pin "6") (pinfunction "BAS_6") (pintype "passive"))
      (node (ref "TP2") (pin "P$1") (pinfunction "1_P$1") (pintype "bidirectional"))
    )
    (net (code "122") (name "Net-(IC6-IN)") (class "Default")
      (node (ref "IC6") (pin "3") (pinfunction "IN_3") (pintype "input"))
      (node (ref "U$7") (pin "TIP") (pinfunction "TIP_TIP") (pintype "bidirectional"))
    )
    (net (code "123") (name "Net-(J1-CDN)") (class "Default")
      (node (ref "J1") (pin "9") (pinfunction "CDN_9") (pintype "bidirectional"))
      (node (ref "R24") (pin "1") (pinfunction "1_1") (pintype "bidirectional"))
    )
    (net (code "124") (name "Net-(J1-DATA1)") (class "Default")
      (node (ref "J1") (pin "8") (pinfunction "DATA1_8") (pintype "bidirectional"))
      (node (ref "R7") (pin "1") (pinfunction "1_1") (pintype "bidirectional"))
    )
    (net (code "125") (name "Net-(J1-DATA2)") (class "Default")
      (node (ref "J1") (pin "1") (pinfunction "DATA2_1") (pintype "bidirectional"))
      (node (ref "R5") (pin "1") (pinfunction "1_1") (pintype "bidirectional"))
    )
    (net (code "126") (name "Net-(LED_EYE-PadA)") (class "Default")
      (node (ref "LED_EYE") (pin "A") (pinfunction "A_A") (pintype "passive"))
      (node (ref "R20") (pin "1") (pinfunction "1_1") (pintype "bidirectional"))
    )
    (net (code "127") (name "Net-(LED_PWR-PadA)") (class "Default")
      (node (ref "LED_PWR") (pin "A") (pinfunction "A_A") (pintype "passive"))
      (node (ref "R14") (pin "1") (pinfunction "1_1") (pintype "bidirectional"))
    )
    (net (code "128") (name "Net-(PORT_MIDI-IN-Pad4)") (class "Default")
      (node (ref "PORT_MIDI-IN") (pin "4") (pinfunction "4_4") (pintype "passive"))
      (node (ref "R38") (pin "2") (pinfunction "2_2") (pintype "bidirectional"))
    )
    (net (code "129") (name "Net-(PORT_MIDI-OUT-Pad4)") (class "Default")
      (node (ref "PORT_MIDI-OUT") (pin "4") (pinfunction "4_4") (pintype "passive"))
      (node (ref "R11") (pin "2") (pinfunction "2_2") (pintype "bidirectional"))
    )
    (net (code "130") (name "Net-(PORT_MIDI-OUT-Pad5)") (class "Default")
      (node (ref "PORT_MIDI-OUT") (pin "5") (pinfunction "5_5") (pintype "passive"))
      (node (ref "R10") (pin "1") (pinfunction "1_1") (pintype "bidirectional"))
    )
    (net (code "131") (name "Net-(PORT_MIDI-THROUGH-Pad4)") (class "Default")
      (node (ref "PORT_MIDI-THROUGH") (pin "4") (pinfunction "4_4") (pintype "passive"))
      (node (ref "R22") (pin "2") (pinfunction "2_2") (pintype "bidirectional"))
    )
    (net (code "132") (name "Net-(PORT_MIDI-THROUGH-Pad5)") (class "Default")
      (node (ref "PORT_MIDI-THROUGH") (pin "5") (pinfunction "5_5") (pintype "passive"))
      (node (ref "R21") (pin "1") (pinfunction "1_1") (pintype "bidirectional"))
    )
    (net (code "133") (name "Net-(R25A-2)") (class "Default")
      (node (ref "R25") (pin "8") (pinfunction "2_8") (pintype "passive"))
      (node (ref "U$1") (pin "5") (pinfunction "LEDA4_5") (pintype "power_in"))
    )
    (net (code "134") (name "Net-(R25B-2)") (class "Default")
      (node (ref "R25") (pin "7") (pinfunction "2_7") (pintype "passive"))
      (node (ref "U$1") (pin "4") (pinfunction "LEDA3_4") (pintype "power_in"))
    )
    (net (code "135") (name "Net-(R25C-2)") (class "Default")
      (node (ref "R25") (pin "6") (pinfunction "2_6") (pintype "passive"))
      (node (ref "U$1") (pin "3") (pinfunction "LEDA2_3") (pintype "power_in"))
    )
    (net (code "136") (name "Net-(R25D-2)") (class "Default")
      (node (ref "R25") (pin "5") (pinfunction "2_5") (pintype "passive"))
      (node (ref "U$1") (pin "2") (pinfunction "LEDA1_2") (pintype "power_in"))
    )
    (net (code "137") (name "Net-(SWD2-SWCLK)") (class "Default")
      (node (ref "SWD2") (pin "4") (pinfunction "SWCLK_4") (pintype "bidirectional"))
      (node (ref "U4") (pin "22") (pinfunction "PTA0/IRQ_0/SWD_CLK_22") (pintype "bidirectional"))
    )
    (net (code "138") (name "Net-(SWD2-SWDIO)") (class "Default")
      (node (ref "SWD2") (pin "2") (pinfunction "SWDIO_2") (pintype "bidirectional"))
      (node (ref "U4") (pin "24") (pinfunction "PTA2/SWD_DIO_24") (pintype "bidirectional"))
    )
    (net (code "139") (name "Net-(U$6-FILT+)") (class "Default")
      (node (ref "C50") (pin "1") (pinfunction "1_1") (pintype "passive"))
      (node (ref "U$6") (pin "6") (pinfunction "FILT+_6") (pintype "bidirectional"))
    )
    (net (code "140") (name "Net-(U1-3A)") (class "Default")
      (node (ref "U1") (pin "5") (pinfunction "3A_5") (pintype "input"))
      (node (ref "U1") (pin "8") (pinfunction "~{4Y}_8") (pintype "output"))
    )
    (net (code "141") (name "Net-(U1-5A)") (class "Default")
      (node (ref "U1") (pin "11") (pinfunction "5A_11") (pintype "input"))
      (node (ref "U1") (pin "12") (pinfunction "~{6Y}_12") (pintype "output"))
    )
    (net (code "142") (name "Net-(U1-~{3Y})") (class "Default")
      (node (ref "R21") (pin "2") (pinfunction "2_2") (pintype "bidirectional"))
      (node (ref "U1") (pin "6") (pinfunction "~{3Y}_6") (pintype "output"))
    )
    (net (code "143") (name "Net-(U1-~{5Y})") (class "Default")
      (node (ref "R10") (pin "2") (pinfunction "2_2") (pintype "bidirectional"))
      (node (ref "U1") (pin "10") (pinfunction "~{5Y}_10") (pintype "output"))
    )
    (net (code "144") (name "Net-(U2-PB6(XTAL1{slash}TOSC1))") (class "Default")
      (node (ref "C38") (pin "2") (pinfunction "2_2") (pintype "bidirectional"))
      (node (ref "U2") (pin "7") (pinfunction "PB6(XTAL1/TOSC1)_7") (pintype "bidirectional"))
      (node (ref "X3") (pin "2") (pinfunction "2_2") (pintype "passive"))
    )
    (net (code "145") (name "Net-(U2-PB7(XTAL2{slash}TOSC2))") (class "Default")
      (node (ref "C39") (pin "2") (pinfunction "2_2") (pintype "bidirectional"))
      (node (ref "U2") (pin "8") (pinfunction "PB7(XTAL2/TOSC2)_8") (pintype "bidirectional"))
      (node (ref "X3") (pin "1") (pinfunction "1_1") (pintype "passive"))
    )
    (net (code "146") (name "Net-(U3-B)") (class "Default")
      (node (ref "R19") (pin "1") (pinfunction "1_1") (pintype "bidirectional"))
      (node (ref "U3") (pin "1") (pinfunction "B_1") (pintype "passive"))
    )
    (net (code "147") (name "Net-(X1-GND1)") (class "Default")
      (node (ref "J2") (pin "E1") (pinfunction "GND_E1") (pintype "bidirectional"))
      (node (ref "J2") (pin "E2") (pinfunction "GND_E2") (pintype "bidirectional"))
      (node (ref "J2") (pin "P1") (pinfunction "GND_P1") (pintype "bidirectional"))
      (node (ref "J2") (pin "P2") (pinfunction "GND_P2") (pintype "bidirectional"))
      (node (ref "L1") (pin "2") (pinfunction "2_2") (pintype "passive"))
      (node (ref "X1") (pin "P$1") (pinfunction "GND1_P$1") (pintype "power_in"))
      (node (ref "X1") (pin "P$2") (pinfunction "GND2_P$2") (pintype "power_in"))
    )
    (net (code "148") (name "unconnected-(BUTTON1-A1-Pad4)") (class "Default")
      (node (ref "BUTTON1") (pin "4") (pinfunction "A1_4") (pintype "bidirectional"))
    )
    (net (code "149") (name "unconnected-(BUTTON1-B1-Pad3)") (class "Default")
      (node (ref "BUTTON1") (pin "3") (pinfunction "B1_3") (pintype "bidirectional"))
    )
    (net (code "150") (name "unconnected-(IC1-ADC0_DM0-Pad10)") (class "Default")
      (node (ref "IC1") (pin "10") (pinfunction "ADC0_DM0_10") (pintype "bidirectional"))
    )
    (net (code "151") (name "unconnected-(IC1-ADC0_DM3-Pad12)") (class "Default")
      (node (ref "IC1") (pin "12") (pinfunction "ADC0_DM3_12") (pintype "bidirectional"))
    )
    (net (code "152") (name "unconnected-(IC1-ADC0_DP0-Pad9)") (class "Default")
      (node (ref "IC1") (pin "9") (pinfunction "ADC0_DP0_9") (pintype "bidirectional"))
    )
    (net (code "153") (name "unconnected-(IC1-ADC0_DP3-Pad11)") (class "Default")
      (node (ref "IC1") (pin "11") (pinfunction "ADC0_DP3_11") (pintype "bidirectional"))
    )
    (net (code "154") (name "unconnected-(IC1-EXTAL32-Pad20)") (class "Default")
      (node (ref "IC1") (pin "20") (pinfunction "EXTAL32_20") (pintype "bidirectional"))
    )
    (net (code "155") (name "unconnected-(IC1-VREF_OUT-Pad17)") (class "Default")
      (node (ref "IC1") (pin "17") (pinfunction "VREF_OUT_17") (pintype "bidirectional"))
    )
    (net (code "156") (name "unconnected-(IC1-XTAL32-Pad19)") (class "Default")
      (node (ref "IC1") (pin "19") (pinfunction "XTAL32_19") (pintype "bidirectional"))
    )
    (net (code "157") (name "unconnected-(IC3A-~{QH}-Pad7)") (class "Default")
      (node (ref "IC3") (pin "7") (pinfunction "~{QH}_7") (pintype "output"))
    )
    (net (code "158") (name "unconnected-(J2-ID-Pad4)") (class "Default")
      (node (ref "J2") (pin "4") (pinfunction "ID_4") (pintype "bidirectional"))
    )
    (net (code "159") (name "unconnected-(JP1-EARTH-NORM-PadP$3)") (class "Default")
      (node (ref "JP1") (pin "P$3") (pinfunction "EARTH-NORM_P$3") (pintype "bidirectional"))
    )
    (net (code "160") (name "unconnected-(JP1-RING-NORM-PadP$5)") (class "Default")
      (node (ref "JP1") (pin "P$5") (pinfunction "RING-NORM_P$5") (pintype "bidirectional"))
    )
    (net (code "161") (name "unconnected-(JP1-TIP-NORM-PadP$7)") (class "Default")
      (node (ref "JP1") (pin "P$7") (pinfunction "TIP-NORM_P$7") (pintype "bidirectional"))
    )
    (net (code "162") (name "unconnected-(PORT_MIDI-IN-Pad1)") (class "Default")
      (node (ref "PORT_MIDI-IN") (pin "1") (pinfunction "1_1") (pintype "passive"))
    )
    (net (code "163") (name "unconnected-(PORT_MIDI-IN-Pad2)") (class "Default")
      (node (ref "PORT_MIDI-IN") (pin "2") (pinfunction "2_2") (pintype "passive"))
    )
    (net (code "164") (name "unconnected-(PORT_MIDI-IN-Pad3)") (class "Default")
      (node (ref "PORT_MIDI-IN") (pin "3") (pinfunction "3_3") (pintype "passive"))
    )
    (net (code "165") (name "unconnected-(PORT_MIDI-OUT-Pad1)") (class "Default")
      (node (ref "PORT_MIDI-OUT") (pin "1") (pinfunction "1_1") (pintype "passive"))
    )
    (net (code "166") (name "unconnected-(PORT_MIDI-OUT-Pad3)") (class "Default")
      (node (ref "PORT_MIDI-OUT") (pin "3") (pinfunction "3_3") (pintype "passive"))
    )
    (net (code "167") (name "unconnected-(PORT_MIDI-THROUGH-Pad1)") (class "Default")
      (node (ref "PORT_MIDI-THROUGH") (pin "1") (pinfunction "1_1") (pintype "passive"))
    )
    (net (code "168") (name "unconnected-(PORT_MIDI-THROUGH-Pad3)") (class "Default")
      (node (ref "PORT_MIDI-THROUGH") (pin "3") (pinfunction "3_3") (pintype "passive"))
    )
    (net (code "169") (name "unconnected-(SWD1-N{slash}C1-Pad7)") (class "Default")
      (node (ref "SWD1") (pin "7") (pinfunction "N/C1_7") (pintype "bidirectional"))
    )
    (net (code "170") (name "unconnected-(SWD2-GND3-Pad9)") (class "Default")
      (node (ref "SWD2") (pin "9") (pinfunction "GND3_9") (pintype "bidirectional"))
    )
    (net (code "171") (name "unconnected-(SWD2-N{slash}C1-Pad7)") (class "Default")
      (node (ref "SWD2") (pin "7") (pinfunction "N/C1_7") (pintype "bidirectional"))
    )
    (net (code "172") (name "unconnected-(SWD2-N{slash}C2-Pad8)") (class "Default")
      (node (ref "SWD2") (pin "8") (pinfunction "N/C2_8") (pintype "bidirectional"))
    )
    (net (code "173") (name "unconnected-(SWD2-SWO-Pad6)") (class "Default")
      (node (ref "SWD2") (pin "6") (pinfunction "SWO_6") (pintype "bidirectional"))
    )
    (net (code "174") (name "unconnected-(U$1-TE-Pad39)") (class "Default")
      (node (ref "U$1") (pin "39") (pinfunction "TE_39") (pintype "input"))
    )
    (net (code "175") (name "unconnected-(U1-~{1Y}-Pad2)") (class "Default")
      (node (ref "U1") (pin "2") (pinfunction "~{1Y}_2") (pintype "output"))
    )
    (net (code "176") (name "unconnected-(U1-~{2Y}-Pad4)") (class "Default")
      (node (ref "U1") (pin "4") (pinfunction "~{2Y}_4") (pintype "output"))
    )
  )
)
